# currentBaseBoard_v7.net
KiCad netlist of a schematic drawn in EAGLE
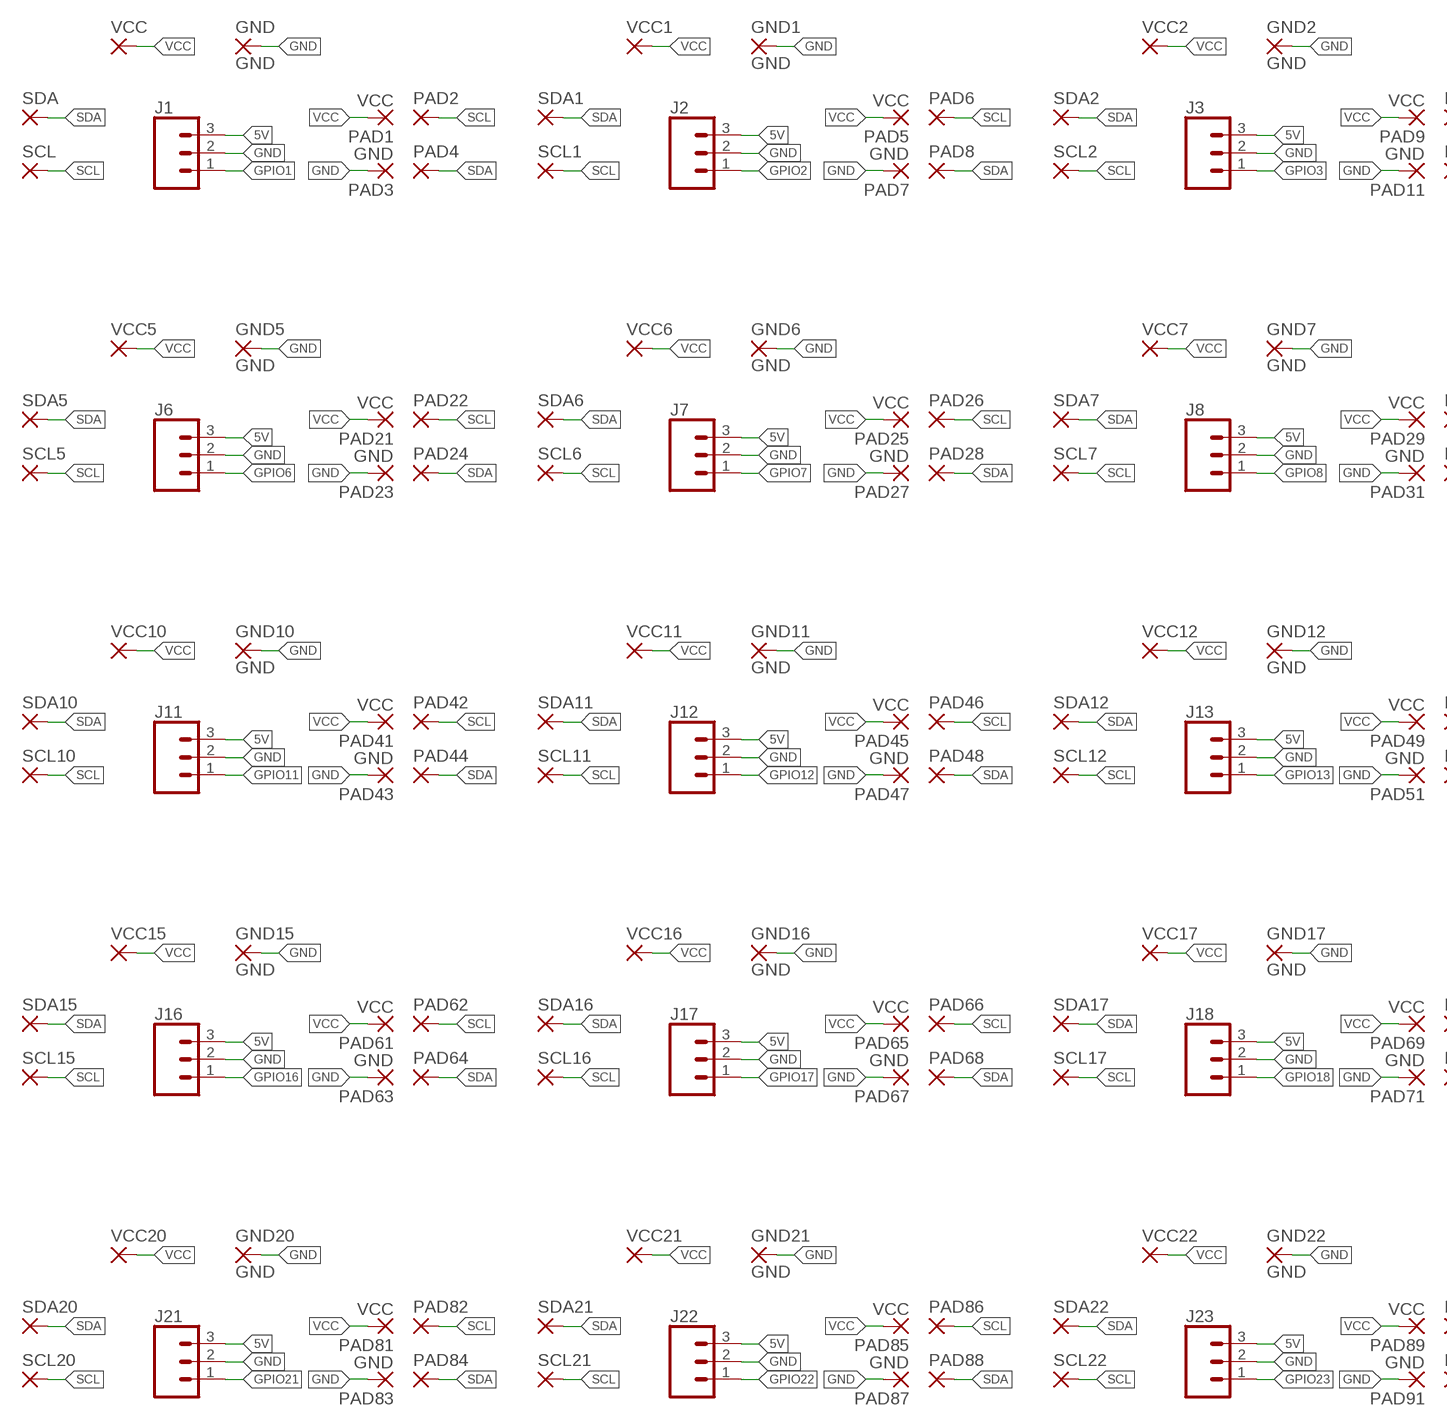
[diagram p0: schematic, sheet 1, part 1 of 2]
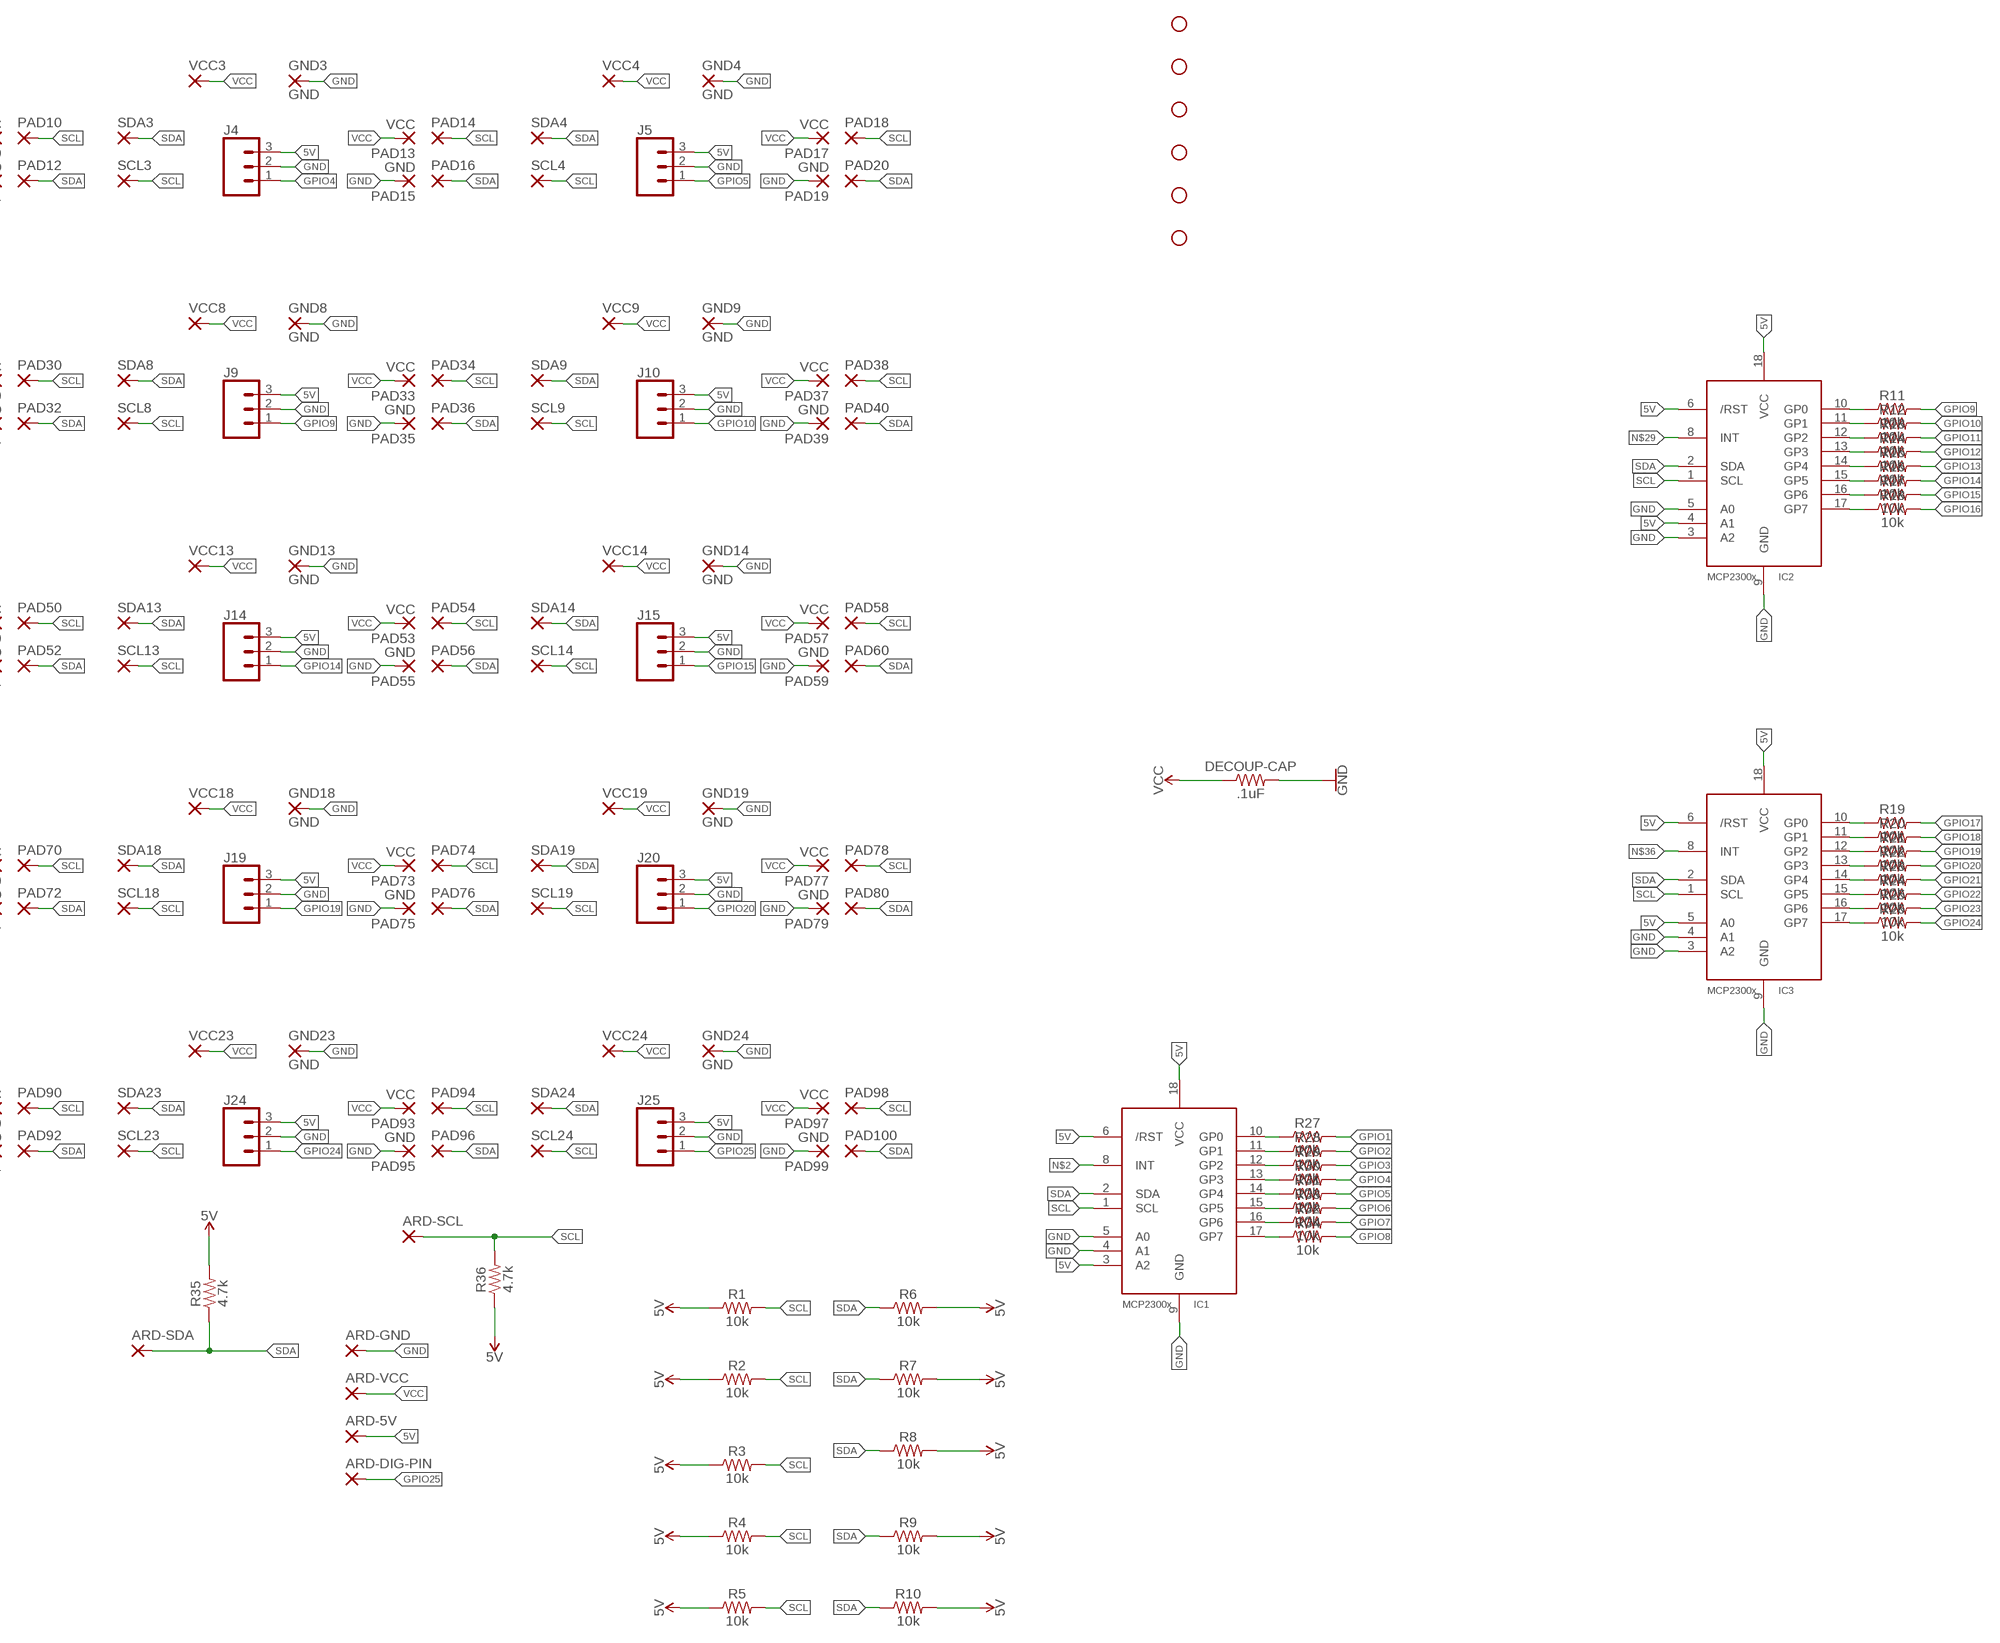
[diagram p1: schematic, sheet 1, part 2 of 2]

(export (version "E")
  (design (tool "Eeschema 10.0.6"))
  (components
    (comp (ref "ARD-5V")
      (value "2,15/1,0")
      (footprint "eagle-import:2,15_1,0")
      (libsource (lib "eagle-import") (part "2,15/1,0"))
    )
    (comp (ref "ARD-DIG-PIN")
      (value "2,15/1,0")
      (footprint "eagle-import:2,15_1,0")
      (libsource (lib "eagle-import") (part "2,15/1,0"))
    )
    (comp (ref "ARD-GND")
      (value "2,15/1,0")
      (footprint "eagle-import:2,15_1,0")
      (libsource (lib "eagle-import") (part "2,15/1,0"))
    )
    (comp (ref "ARD-SCL")
      (value "2,15/1,0")
      (footprint "eagle-import:2,15_1,0")
      (libsource (lib "eagle-import") (part "2,15/1,0"))
    )
    (comp (ref "ARD-SDA")
      (value "2,15/1,0")
      (footprint "eagle-import:2,15_1,0")
      (libsource (lib "eagle-import") (part "2,15/1,0"))
    )
    (comp (ref "ARD-VCC")
      (value "2,15/1,0")
      (footprint "eagle-import:2,15_1,0")
      (libsource (lib "eagle-import") (part "2,15/1,0"))
    )
    (comp (ref "DECOUP-CAP")
      (value ".1uF")
      (footprint "eagle-import:AXIAL-0.3")
      (libsource (lib "eagle-import") (part "10KOHM-HORIZ-1/6W-5%"))
    )
    (comp (ref "GND")
      (value "GND")
      (footprint "eagle-import:2,15_1,0")
      (libsource (lib "eagle-import") (part "2,15/1,0"))
    )
    (comp (ref "GND1")
      (value "GND")
      (footprint "eagle-import:2,15_1,0")
      (libsource (lib "eagle-import") (part "2,15/1,0"))
    )
    (comp (ref "GND2")
      (value "GND")
      (footprint "eagle-import:2,15_1,0")
      (libsource (lib "eagle-import") (part "2,15/1,0"))
    )
    (comp (ref "GND3")
      (value "GND")
      (footprint "eagle-import:2,15_1,0")
      (libsource (lib "eagle-import") (part "2,15/1,0"))
    )
    (comp (ref "GND4")
      (value "GND")
      (footprint "eagle-import:2,15_1,0")
      (libsource (lib "eagle-import") (part "2,15/1,0"))
    )
    (comp (ref "GND5")
      (value "GND")
      (footprint "eagle-import:2,15_1,0")
      (libsource (lib "eagle-import") (part "2,15/1,0"))
    )
    (comp (ref "GND6")
      (value "GND")
      (footprint "eagle-import:2,15_1,0")
      (libsource (lib "eagle-import") (part "2,15/1,0"))
    )
    (comp (ref "GND7")
      (value "GND")
      (footprint "eagle-import:2,15_1,0")
      (libsource (lib "eagle-import") (part "2,15/1,0"))
    )
    (comp (ref "GND8")
      (value "GND")
      (footprint "eagle-import:2,15_1,0")
      (libsource (lib "eagle-import") (part "2,15/1,0"))
    )
    (comp (ref "GND9")
      (value "GND")
      (footprint "eagle-import:2,15_1,0")
      (libsource (lib "eagle-import") (part "2,15/1,0"))
    )
    (comp (ref "GND10")
      (value "GND")
      (footprint "eagle-import:2,15_1,0")
      (libsource (lib "eagle-import") (part "2,15/1,0"))
    )
    (comp (ref "GND11")
      (value "GND")
      (footprint "eagle-import:2,15_1,0")
      (libsource (lib "eagle-import") (part "2,15/1,0"))
    )
    (comp (ref "GND12")
      (value "GND")
      (footprint "eagle-import:2,15_1,0")
      (libsource (lib "eagle-import") (part "2,15/1,0"))
    )
    (comp (ref "GND13")
      (value "GND")
      (footprint "eagle-import:2,15_1,0")
      (libsource (lib "eagle-import") (part "2,15/1,0"))
    )
    (comp (ref "GND14")
      (value "GND")
      (footprint "eagle-import:2,15_1,0")
      (libsource (lib "eagle-import") (part "2,15/1,0"))
    )
    (comp (ref "GND15")
      (value "GND")
      (footprint "eagle-import:2,15_1,0")
      (libsource (lib "eagle-import") (part "2,15/1,0"))
    )
    (comp (ref "GND16")
      (value "GND")
      (footprint "eagle-import:2,15_1,0")
      (libsource (lib "eagle-import") (part "2,15/1,0"))
    )
    (comp (ref "GND17")
      (value "GND")
      (footprint "eagle-import:2,15_1,0")
      (libsource (lib "eagle-import") (part "2,15/1,0"))
    )
    (comp (ref "GND18")
      (value "GND")
      (footprint "eagle-import:2,15_1,0")
      (libsource (lib "eagle-import") (part "2,15/1,0"))
    )
    (comp (ref "GND19")
      (value "GND")
      (footprint "eagle-import:2,15_1,0")
      (libsource (lib "eagle-import") (part "2,15/1,0"))
    )
    (comp (ref "GND20")
      (value "GND")
      (footprint "eagle-import:2,15_1,0")
      (libsource (lib "eagle-import") (part "2,15/1,0"))
    )
    (comp (ref "GND21")
      (value "GND")
      (footprint "eagle-import:2,15_1,0")
      (libsource (lib "eagle-import") (part "2,15/1,0"))
    )
    (comp (ref "GND22")
      (value "GND")
      (footprint "eagle-import:2,15_1,0")
      (libsource (lib "eagle-import") (part "2,15/1,0"))
    )
    (comp (ref "GND23")
      (value "GND")
      (footprint "eagle-import:2,15_1,0")
      (libsource (lib "eagle-import") (part "2,15/1,0"))
    )
    (comp (ref "GND24")
      (value "GND")
      (footprint "eagle-import:2,15_1,0")
      (libsource (lib "eagle-import") (part "2,15/1,0"))
    )
    (comp (ref "H1")
      (value "STAND-OFF")
      (footprint "eagle-import:STAND-OFF")
      (libsource (lib "eagle-import") (part "STAND-OFF"))
    )
    (comp (ref "H2")
      (value "STAND-OFF")
      (footprint "eagle-import:STAND-OFF")
      (libsource (lib "eagle-import") (part "STAND-OFF"))
    )
    (comp (ref "H3")
      (value "STAND-OFF")
      (footprint "eagle-import:STAND-OFF")
      (libsource (lib "eagle-import") (part "STAND-OFF"))
    )
    (comp (ref "H4")
      (value "STAND-OFF")
      (footprint "eagle-import:STAND-OFF")
      (libsource (lib "eagle-import") (part "STAND-OFF"))
    )
    (comp (ref "H5")
      (value "STAND-OFF")
      (footprint "eagle-import:STAND-OFF")
      (libsource (lib "eagle-import") (part "STAND-OFF"))
    )
    (comp (ref "H6")
      (value "STAND-OFF")
      (footprint "eagle-import:STAND-OFF")
      (libsource (lib "eagle-import") (part "STAND-OFF"))
    )
    (comp (ref "IC1")
      (value "MCP23008/P")
      (footprint "eagle-import:DIL18")
      (libsource (lib "eagle-import") (part "MCP23008/P"))
    )
    (comp (ref "IC2")
      (value "MCP23008/P")
      (footprint "eagle-import:DIL18")
      (libsource (lib "eagle-import") (part "MCP23008/P"))
    )
    (comp (ref "IC3")
      (value "MCP23008/P")
      (footprint "eagle-import:DIL18")
      (libsource (lib "eagle-import") (part "MCP23008/P"))
    )
    (comp (ref "J1")
      (value "CONN_03")
      (footprint "eagle-import:1X03")
      (libsource (lib "eagle-import") (part "CONN_03"))
    )
    (comp (ref "J2")
      (value "CONN_03")
      (footprint "eagle-import:1X03")
      (libsource (lib "eagle-import") (part "CONN_03"))
    )
    (comp (ref "J3")
      (value "CONN_03")
      (footprint "eagle-import:1X03")
      (libsource (lib "eagle-import") (part "CONN_03"))
    )
    (comp (ref "J4")
      (value "CONN_03")
      (footprint "eagle-import:1X03")
      (libsource (lib "eagle-import") (part "CONN_03"))
    )
    (comp (ref "J5")
      (value "CONN_03")
      (footprint "eagle-import:1X03")
      (libsource (lib "eagle-import") (part "CONN_03"))
    )
    (comp (ref "J6")
      (value "CONN_03")
      (footprint "eagle-import:1X03")
      (libsource (lib "eagle-import") (part "CONN_03"))
    )
    (comp (ref "J7")
      (value "CONN_03")
      (footprint "eagle-import:1X03")
      (libsource (lib "eagle-import") (part "CONN_03"))
    )
    (comp (ref "J8")
      (value "CONN_03")
      (footprint "eagle-import:1X03")
      (libsource (lib "eagle-import") (part "CONN_03"))
    )
    (comp (ref "J9")
      (value "CONN_03")
      (footprint "eagle-import:1X03")
      (libsource (lib "eagle-import") (part "CONN_03"))
    )
    (comp (ref "J10")
      (value "CONN_03")
      (footprint "eagle-import:1X03")
      (libsource (lib "eagle-import") (part "CONN_03"))
    )
    (comp (ref "J11")
      (value "CONN_03")
      (footprint "eagle-import:1X03")
      (libsource (lib "eagle-import") (part "CONN_03"))
    )
    (comp (ref "J12")
      (value "CONN_03")
      (footprint "eagle-import:1X03")
      (libsource (lib "eagle-import") (part "CONN_03"))
    )
    (comp (ref "J13")
      (value "CONN_03")
      (footprint "eagle-import:1X03")
      (libsource (lib "eagle-import") (part "CONN_03"))
    )
    (comp (ref "J14")
      (value "CONN_03")
      (footprint "eagle-import:1X03")
      (libsource (lib "eagle-import") (part "CONN_03"))
    )
    (comp (ref "J15")
      (value "CONN_03")
      (footprint "eagle-import:1X03")
      (libsource (lib "eagle-import") (part "CONN_03"))
    )
    (comp (ref "J16")
      (value "CONN_03")
      (footprint "eagle-import:1X03")
      (libsource (lib "eagle-import") (part "CONN_03"))
    )
    (comp (ref "J17")
      (value "CONN_03")
      (footprint "eagle-import:1X03")
      (libsource (lib "eagle-import") (part "CONN_03"))
    )
    (comp (ref "J18")
      (value "CONN_03")
      (footprint "eagle-import:1X03")
      (libsource (lib "eagle-import") (part "CONN_03"))
    )
    (comp (ref "J19")
      (value "CONN_03")
      (footprint "eagle-import:1X03")
      (libsource (lib "eagle-import") (part "CONN_03"))
    )
    (comp (ref "J20")
      (value "CONN_03")
      (footprint "eagle-import:1X03")
      (libsource (lib "eagle-import") (part "CONN_03"))
    )
    (comp (ref "J21")
      (value "CONN_03")
      (footprint "eagle-import:1X03")
      (libsource (lib "eagle-import") (part "CONN_03"))
    )
    (comp (ref "J22")
      (value "CONN_03")
      (footprint "eagle-import:1X03")
      (libsource (lib "eagle-import") (part "CONN_03"))
    )
    (comp (ref "J23")
      (value "CONN_03")
      (footprint "eagle-import:1X03")
      (libsource (lib "eagle-import") (part "CONN_03"))
    )
    (comp (ref "J24")
      (value "CONN_03")
      (footprint "eagle-import:1X03")
      (libsource (lib "eagle-import") (part "CONN_03"))
    )
    (comp (ref "J25")
      (value "CONN_03")
      (footprint "eagle-import:1X03")
      (libsource (lib "eagle-import") (part "CONN_03"))
    )
    (comp (ref "PAD1")
      (value "VCC")
      (footprint "eagle-import:2,15_1,0")
      (libsource (lib "eagle-import") (part "2,15/1,0"))
    )
    (comp (ref "PAD2")
      (value "2,15/1,0")
      (footprint "eagle-import:2,15_1,0")
      (libsource (lib "eagle-import") (part "2,15/1,0"))
    )
    (comp (ref "PAD3")
      (value "GND")
      (footprint "eagle-import:2,15_1,0")
      (libsource (lib "eagle-import") (part "2,15/1,0"))
    )
    (comp (ref "PAD4")
      (value "2,15/1,0")
      (footprint "eagle-import:2,15_1,0")
      (libsource (lib "eagle-import") (part "2,15/1,0"))
    )
    (comp (ref "PAD5")
      (value "VCC")
      (footprint "eagle-import:2,15_1,0")
      (libsource (lib "eagle-import") (part "2,15/1,0"))
    )
    (comp (ref "PAD6")
      (value "2,15/1,0")
      (footprint "eagle-import:2,15_1,0")
      (libsource (lib "eagle-import") (part "2,15/1,0"))
    )
    (comp (ref "PAD7")
      (value "GND")
      (footprint "eagle-import:2,15_1,0")
      (libsource (lib "eagle-import") (part "2,15/1,0"))
    )
    (comp (ref "PAD8")
      (value "2,15/1,0")
      (footprint "eagle-import:2,15_1,0")
      (libsource (lib "eagle-import") (part "2,15/1,0"))
    )
    (comp (ref "PAD9")
      (value "VCC")
      (footprint "eagle-import:2,15_1,0")
      (libsource (lib "eagle-import") (part "2,15/1,0"))
    )
    (comp (ref "PAD10")
      (value "2,15/1,0")
      (footprint "eagle-import:2,15_1,0")
      (libsource (lib "eagle-import") (part "2,15/1,0"))
    )
    (comp (ref "PAD11")
      (value "GND")
      (footprint "eagle-import:2,15_1,0")
      (libsource (lib "eagle-import") (part "2,15/1,0"))
    )
    (comp (ref "PAD12")
      (value "2,15/1,0")
      (footprint "eagle-import:2,15_1,0")
      (libsource (lib "eagle-import") (part "2,15/1,0"))
    )
    (comp (ref "PAD13")
      (value "VCC")
      (footprint "eagle-import:2,15_1,0")
      (libsource (lib "eagle-import") (part "2,15/1,0"))
    )
    (comp (ref "PAD14")
      (value "2,15/1,0")
      (footprint "eagle-import:2,15_1,0")
      (libsource (lib "eagle-import") (part "2,15/1,0"))
    )
    (comp (ref "PAD15")
      (value "GND")
      (footprint "eagle-import:2,15_1,0")
      (libsource (lib "eagle-import") (part "2,15/1,0"))
    )
    (comp (ref "PAD16")
      (value "2,15/1,0")
      (footprint "eagle-import:2,15_1,0")
      (libsource (lib "eagle-import") (part "2,15/1,0"))
    )
    (comp (ref "PAD17")
      (value "VCC")
      (footprint "eagle-import:2,15_1,0")
      (libsource (lib "eagle-import") (part "2,15/1,0"))
    )
    (comp (ref "PAD18")
      (value "2,15/1,0")
      (footprint "eagle-import:2,15_1,0")
      (libsource (lib "eagle-import") (part "2,15/1,0"))
    )
    (comp (ref "PAD19")
      (value "GND")
      (footprint "eagle-import:2,15_1,0")
      (libsource (lib "eagle-import") (part "2,15/1,0"))
    )
    (comp (ref "PAD20")
      (value "2,15/1,0")
      (footprint "eagle-import:2,15_1,0")
      (libsource (lib "eagle-import") (part "2,15/1,0"))
    )
    (comp (ref "PAD21")
      (value "VCC")
      (footprint "eagle-import:2,15_1,0")
      (libsource (lib "eagle-import") (part "2,15/1,0"))
    )
    (comp (ref "PAD22")
      (value "2,15/1,0")
      (footprint "eagle-import:2,15_1,0")
      (libsource (lib "eagle-import") (part "2,15/1,0"))
    )
    (comp (ref "PAD23")
      (value "GND")
      (footprint "eagle-import:2,15_1,0")
      (libsource (lib "eagle-import") (part "2,15/1,0"))
    )
    (comp (ref "PAD24")
      (value "2,15/1,0")
      (footprint "eagle-import:2,15_1,0")
      (libsource (lib "eagle-import") (part "2,15/1,0"))
    )
    (comp (ref "PAD25")
      (value "VCC")
      (footprint "eagle-import:2,15_1,0")
      (libsource (lib "eagle-import") (part "2,15/1,0"))
    )
    (comp (ref "PAD26")
      (value "2,15/1,0")
      (footprint "eagle-import:2,15_1,0")
      (libsource (lib "eagle-import") (part "2,15/1,0"))
    )
    (comp (ref "PAD27")
      (value "GND")
      (footprint "eagle-import:2,15_1,0")
      (libsource (lib "eagle-import") (part "2,15/1,0"))
    )
    (comp (ref "PAD28")
      (value "2,15/1,0")
      (footprint "eagle-import:2,15_1,0")
      (libsource (lib "eagle-import") (part "2,15/1,0"))
    )
    (comp (ref "PAD29")
      (value "VCC")
      (footprint "eagle-import:2,15_1,0")
      (libsource (lib "eagle-import") (part "2,15/1,0"))
    )
    (comp (ref "PAD30")
      (value "2,15/1,0")
      (footprint "eagle-import:2,15_1,0")
      (libsource (lib "eagle-import") (part "2,15/1,0"))
    )
    (comp (ref "PAD31")
      (value "GND")
      (footprint "eagle-import:2,15_1,0")
      (libsource (lib "eagle-import") (part "2,15/1,0"))
    )
    (comp (ref "PAD32")
      (value "2,15/1,0")
      (footprint "eagle-import:2,15_1,0")
      (libsource (lib "eagle-import") (part "2,15/1,0"))
    )
    (comp (ref "PAD33")
      (value "VCC")
      (footprint "eagle-import:2,15_1,0")
      (libsource (lib "eagle-import") (part "2,15/1,0"))
    )
    (comp (ref "PAD34")
      (value "2,15/1,0")
      (footprint "eagle-import:2,15_1,0")
      (libsource (lib "eagle-import") (part "2,15/1,0"))
    )
    (comp (ref "PAD35")
      (value "GND")
      (footprint "eagle-import:2,15_1,0")
      (libsource (lib "eagle-import") (part "2,15/1,0"))
    )
    (comp (ref "PAD36")
      (value "2,15/1,0")
      (footprint "eagle-import:2,15_1,0")
      (libsource (lib "eagle-import") (part "2,15/1,0"))
    )
    (comp (ref "PAD37")
      (value "VCC")
      (footprint "eagle-import:2,15_1,0")
      (libsource (lib "eagle-import") (part "2,15/1,0"))
    )
    (comp (ref "PAD38")
      (value "2,15/1,0")
      (footprint "eagle-import:2,15_1,0")
      (libsource (lib "eagle-import") (part "2,15/1,0"))
    )
    (comp (ref "PAD39")
      (value "GND")
      (footprint "eagle-import:2,15_1,0")
      (libsource (lib "eagle-import") (part "2,15/1,0"))
    )
    (comp (ref "PAD40")
      (value "2,15/1,0")
      (footprint "eagle-import:2,15_1,0")
      (libsource (lib "eagle-import") (part "2,15/1,0"))
    )
    (comp (ref "PAD41")
      (value "VCC")
      (footprint "eagle-import:2,15_1,0")
      (libsource (lib "eagle-import") (part "2,15/1,0"))
    )
    (comp (ref "PAD42")
      (value "2,15/1,0")
      (footprint "eagle-import:2,15_1,0")
      (libsource (lib "eagle-import") (part "2,15/1,0"))
    )
    (comp (ref "PAD43")
      (value "GND")
      (footprint "eagle-import:2,15_1,0")
      (libsource (lib "eagle-import") (part "2,15/1,0"))
    )
    (comp (ref "PAD44")
      (value "2,15/1,0")
      (footprint "eagle-import:2,15_1,0")
      (libsource (lib "eagle-import") (part "2,15/1,0"))
    )
    (comp (ref "PAD45")
      (value "VCC")
      (footprint "eagle-import:2,15_1,0")
      (libsource (lib "eagle-import") (part "2,15/1,0"))
    )
    (comp (ref "PAD46")
      (value "2,15/1,0")
      (footprint "eagle-import:2,15_1,0")
      (libsource (lib "eagle-import") (part "2,15/1,0"))
    )
    (comp (ref "PAD47")
      (value "GND")
      (footprint "eagle-import:2,15_1,0")
      (libsource (lib "eagle-import") (part "2,15/1,0"))
    )
    (comp (ref "PAD48")
      (value "2,15/1,0")
      (footprint "eagle-import:2,15_1,0")
      (libsource (lib "eagle-import") (part "2,15/1,0"))
    )
    (comp (ref "PAD49")
      (value "VCC")
      (footprint "eagle-import:2,15_1,0")
      (libsource (lib "eagle-import") (part "2,15/1,0"))
    )
    (comp (ref "PAD50")
      (value "2,15/1,0")
      (footprint "eagle-import:2,15_1,0")
      (libsource (lib "eagle-import") (part "2,15/1,0"))
    )
    (comp (ref "PAD51")
      (value "GND")
      (footprint "eagle-import:2,15_1,0")
      (libsource (lib "eagle-import") (part "2,15/1,0"))
    )
    (comp (ref "PAD52")
      (value "2,15/1,0")
      (footprint "eagle-import:2,15_1,0")
      (libsource (lib "eagle-import") (part "2,15/1,0"))
    )
    (comp (ref "PAD53")
      (value "VCC")
      (footprint "eagle-import:2,15_1,0")
      (libsource (lib "eagle-import") (part "2,15/1,0"))
    )
    (comp (ref "PAD54")
      (value "2,15/1,0")
      (footprint "eagle-import:2,15_1,0")
      (libsource (lib "eagle-import") (part "2,15/1,0"))
    )
    (comp (ref "PAD55")
      (value "GND")
      (footprint "eagle-import:2,15_1,0")
      (libsource (lib "eagle-import") (part "2,15/1,0"))
    )
    (comp (ref "PAD56")
      (value "2,15/1,0")
      (footprint "eagle-import:2,15_1,0")
      (libsource (lib "eagle-import") (part "2,15/1,0"))
    )
    (comp (ref "PAD57")
      (value "VCC")
      (footprint "eagle-import:2,15_1,0")
      (libsource (lib "eagle-import") (part "2,15/1,0"))
    )
    (comp (ref "PAD58")
      (value "2,15/1,0")
      (footprint "eagle-import:2,15_1,0")
      (libsource (lib "eagle-import") (part "2,15/1,0"))
    )
    (comp (ref "PAD59")
      (value "GND")
      (footprint "eagle-import:2,15_1,0")
      (libsource (lib "eagle-import") (part "2,15/1,0"))
    )
    (comp (ref "PAD60")
      (value "2,15/1,0")
      (footprint "eagle-import:2,15_1,0")
      (libsource (lib "eagle-import") (part "2,15/1,0"))
    )
    (comp (ref "PAD61")
      (value "VCC")
      (footprint "eagle-import:2,15_1,0")
      (libsource (lib "eagle-import") (part "2,15/1,0"))
    )
    (comp (ref "PAD62")
      (value "2,15/1,0")
      (footprint "eagle-import:2,15_1,0")
      (libsource (lib "eagle-import") (part "2,15/1,0"))
    )
    (comp (ref "PAD63")
      (value "GND")
      (footprint "eagle-import:2,15_1,0")
      (libsource (lib "eagle-import") (part "2,15/1,0"))
    )
    (comp (ref "PAD64")
      (value "2,15/1,0")
      (footprint "eagle-import:2,15_1,0")
      (libsource (lib "eagle-import") (part "2,15/1,0"))
    )
    (comp (ref "PAD65")
      (value "VCC")
      (footprint "eagle-import:2,15_1,0")
      (libsource (lib "eagle-import") (part "2,15/1,0"))
    )
    (comp (ref "PAD66")
      (value "2,15/1,0")
      (footprint "eagle-import:2,15_1,0")
      (libsource (lib "eagle-import") (part "2,15/1,0"))
    )
    (comp (ref "PAD67")
      (value "GND")
      (footprint "eagle-import:2,15_1,0")
      (libsource (lib "eagle-import") (part "2,15/1,0"))
    )
    (comp (ref "PAD68")
      (value "2,15/1,0")
      (footprint "eagle-import:2,15_1,0")
      (libsource (lib "eagle-import") (part "2,15/1,0"))
    )
    (comp (ref "PAD69")
      (value "VCC")
      (footprint "eagle-import:2,15_1,0")
      (libsource (lib "eagle-import") (part "2,15/1,0"))
    )
    (comp (ref "PAD70")
      (value "2,15/1,0")
      (footprint "eagle-import:2,15_1,0")
      (libsource (lib "eagle-import") (part "2,15/1,0"))
    )
    (comp (ref "PAD71")
      (value "GND")
      (footprint "eagle-import:2,15_1,0")
      (libsource (lib "eagle-import") (part "2,15/1,0"))
    )
    (comp (ref "PAD72")
      (value "2,15/1,0")
      (footprint "eagle-import:2,15_1,0")
      (libsource (lib "eagle-import") (part "2,15/1,0"))
    )
    (comp (ref "PAD73")
      (value "VCC")
      (footprint "eagle-import:2,15_1,0")
      (libsource (lib "eagle-import") (part "2,15/1,0"))
    )
    (comp (ref "PAD74")
      (value "2,15/1,0")
      (footprint "eagle-import:2,15_1,0")
      (libsource (lib "eagle-import") (part "2,15/1,0"))
    )
    (comp (ref "PAD75")
      (value "GND")
      (footprint "eagle-import:2,15_1,0")
      (libsource (lib "eagle-import") (part "2,15/1,0"))
    )
    (comp (ref "PAD76")
      (value "2,15/1,0")
      (footprint "eagle-import:2,15_1,0")
      (libsource (lib "eagle-import") (part "2,15/1,0"))
    )
    (comp (ref "PAD77")
      (value "VCC")
      (footprint "eagle-import:2,15_1,0")
      (libsource (lib "eagle-import") (part "2,15/1,0"))
    )
    (comp (ref "PAD78")
      (value "2,15/1,0")
      (footprint "eagle-import:2,15_1,0")
      (libsource (lib "eagle-import") (part "2,15/1,0"))
    )
    (comp (ref "PAD79")
      (value "GND")
      (footprint "eagle-import:2,15_1,0")
      (libsource (lib "eagle-import") (part "2,15/1,0"))
    )
    (comp (ref "PAD80")
      (value "2,15/1,0")
      (footprint "eagle-import:2,15_1,0")
      (libsource (lib "eagle-import") (part "2,15/1,0"))
    )
    (comp (ref "PAD81")
      (value "VCC")
      (footprint "eagle-import:2,15_1,0")
      (libsource (lib "eagle-import") (part "2,15/1,0"))
    )
    (comp (ref "PAD82")
      (value "2,15/1,0")
      (footprint "eagle-import:2,15_1,0")
      (libsource (lib "eagle-import") (part "2,15/1,0"))
    )
    (comp (ref "PAD83")
      (value "GND")
      (footprint "eagle-import:2,15_1,0")
      (libsource (lib "eagle-import") (part "2,15/1,0"))
    )
    (comp (ref "PAD84")
      (value "2,15/1,0")
      (footprint "eagle-import:2,15_1,0")
      (libsource (lib "eagle-import") (part "2,15/1,0"))
    )
    (comp (ref "PAD85")
      (value "VCC")
      (footprint "eagle-import:2,15_1,0")
      (libsource (lib "eagle-import") (part "2,15/1,0"))
    )
    (comp (ref "PAD86")
      (value "2,15/1,0")
      (footprint "eagle-import:2,15_1,0")
      (libsource (lib "eagle-import") (part "2,15/1,0"))
    )
    (comp (ref "PAD87")
      (value "GND")
      (footprint "eagle-import:2,15_1,0")
      (libsource (lib "eagle-import") (part "2,15/1,0"))
    )
    (comp (ref "PAD88")
      (value "2,15/1,0")
      (footprint "eagle-import:2,15_1,0")
      (libsource (lib "eagle-import") (part "2,15/1,0"))
    )
    (comp (ref "PAD89")
      (value "VCC")
      (footprint "eagle-import:2,15_1,0")
      (libsource (lib "eagle-import") (part "2,15/1,0"))
    )
    (comp (ref "PAD90")
      (value "2,15/1,0")
      (footprint "eagle-import:2,15_1,0")
      (libsource (lib "eagle-import") (part "2,15/1,0"))
    )
    (comp (ref "PAD91")
      (value "GND")
      (footprint "eagle-import:2,15_1,0")
      (libsource (lib "eagle-import") (part "2,15/1,0"))
    )
    (comp (ref "PAD92")
      (value "2,15/1,0")
      (footprint "eagle-import:2,15_1,0")
      (libsource (lib "eagle-import") (part "2,15/1,0"))
    )
    (comp (ref "PAD93")
      (value "VCC")
      (footprint "eagle-import:2,15_1,0")
      (libsource (lib "eagle-import") (part "2,15/1,0"))
    )
    (comp (ref "PAD94")
      (value "2,15/1,0")
      (footprint "eagle-import:2,15_1,0")
      (libsource (lib "eagle-import") (part "2,15/1,0"))
    )
    (comp (ref "PAD95")
      (value "GND")
      (footprint "eagle-import:2,15_1,0")
      (libsource (lib "eagle-import") (part "2,15/1,0"))
    )
    (comp (ref "PAD96")
      (value "2,15/1,0")
      (footprint "eagle-import:2,15_1,0")
      (libsource (lib "eagle-import") (part "2,15/1,0"))
    )
    (comp (ref "PAD97")
      (value "VCC")
      (footprint "eagle-import:2,15_1,0")
      (libsource (lib "eagle-import") (part "2,15/1,0"))
    )
    (comp (ref "PAD98")
      (value "2,15/1,0")
      (footprint "eagle-import:2,15_1,0")
      (libsource (lib "eagle-import") (part "2,15/1,0"))
    )
    (comp (ref "PAD99")
      (value "GND")
      (footprint "eagle-import:2,15_1,0")
      (libsource (lib "eagle-import") (part "2,15/1,0"))
    )
    (comp (ref "PAD100")
      (value "2,15/1,0")
      (footprint "eagle-import:2,15_1,0")
      (libsource (lib "eagle-import") (part "2,15/1,0"))
    )
    (comp (ref "R1")
      (value "10k")
      (footprint "eagle-import:AXIAL-0.3")
      (libsource (lib "eagle-import") (part "10KOHM-HORIZ-1/4W-1%"))
    )
    (comp (ref "R2")
      (value "10k")
      (footprint "eagle-import:AXIAL-0.3")
      (libsource (lib "eagle-import") (part "10KOHM-HORIZ-1/4W-1%"))
    )
    (comp (ref "R3")
      (value "10k")
      (footprint "eagle-import:AXIAL-0.3")
      (libsource (lib "eagle-import") (part "10KOHM-HORIZ-1/4W-1%"))
    )
    (comp (ref "R4")
      (value "10k")
      (footprint "eagle-import:AXIAL-0.3")
      (libsource (lib "eagle-import") (part "10KOHM-HORIZ-1/4W-1%"))
    )
    (comp (ref "R5")
      (value "10k")
      (footprint "eagle-import:AXIAL-0.3")
      (libsource (lib "eagle-import") (part "10KOHM-HORIZ-1/4W-1%"))
    )
    (comp (ref "R6")
      (value "10k")
      (footprint "eagle-import:AXIAL-0.3")
      (libsource (lib "eagle-import") (part "10KOHM-HORIZ-1/4W-1%"))
    )
    (comp (ref "R7")
      (value "10k")
      (footprint "eagle-import:AXIAL-0.3")
      (libsource (lib "eagle-import") (part "10KOHM-HORIZ-1/4W-1%"))
    )
    (comp (ref "R8")
      (value "10k")
      (footprint "eagle-import:AXIAL-0.3")
      (libsource (lib "eagle-import") (part "10KOHM-HORIZ-1/4W-1%"))
    )
    (comp (ref "R9")
      (value "10k")
      (footprint "eagle-import:AXIAL-0.3")
      (libsource (lib "eagle-import") (part "10KOHM-HORIZ-1/4W-1%"))
    )
    (comp (ref "R10")
      (value "10k")
      (footprint "eagle-import:AXIAL-0.3")
      (libsource (lib "eagle-import") (part "10KOHM-HORIZ-1/4W-1%"))
    )
    (comp (ref "R11")
      (value "10k")
      (footprint "eagle-import:AXIAL-0.3")
      (libsource (lib "eagle-import") (part "10KOHM-HORIZ-1/6W-5%"))
    )
    (comp (ref "R12")
      (value "10k")
      (footprint "eagle-import:AXIAL-0.3")
      (libsource (lib "eagle-import") (part "10KOHM-HORIZ-1/6W-5%"))
    )
    (comp (ref "R13")
      (value "10k")
      (footprint "eagle-import:AXIAL-0.3")
      (libsource (lib "eagle-import") (part "10KOHM-HORIZ-1/6W-5%"))
    )
    (comp (ref "R14")
      (value "10k")
      (footprint "eagle-import:AXIAL-0.3")
      (libsource (lib "eagle-import") (part "10KOHM-HORIZ-1/6W-5%"))
    )
    (comp (ref "R15")
      (value "10k")
      (footprint "eagle-import:AXIAL-0.3")
      (libsource (lib "eagle-import") (part "10KOHM-HORIZ-1/6W-5%"))
    )
    (comp (ref "R16")
      (value "10k")
      (footprint "eagle-import:AXIAL-0.3")
      (libsource (lib "eagle-import") (part "10KOHM-HORIZ-1/6W-5%"))
    )
    (comp (ref "R17")
      (value "10k")
      (footprint "eagle-import:AXIAL-0.3")
      (libsource (lib "eagle-import") (part "10KOHM-HORIZ-1/6W-5%"))
    )
    (comp (ref "R18")
      (value "10k")
      (footprint "eagle-import:AXIAL-0.3")
      (libsource (lib "eagle-import") (part "10KOHM-HORIZ-1/6W-5%"))
    )
    (comp (ref "R19")
      (value "10k")
      (footprint "eagle-import:AXIAL-0.3")
      (libsource (lib "eagle-import") (part "10KOHM-HORIZ-1/6W-5%"))
    )
    (comp (ref "R20")
      (value "10k")
      (footprint "eagle-import:AXIAL-0.3")
      (libsource (lib "eagle-import") (part "10KOHM-HORIZ-1/6W-5%"))
    )
    (comp (ref "R21")
      (value "10k")
      (footprint "eagle-import:AXIAL-0.3")
      (libsource (lib "eagle-import") (part "10KOHM-HORIZ-1/6W-5%"))
    )
    (comp (ref "R22")
      (value "10k")
      (footprint "eagle-import:AXIAL-0.3")
      (libsource (lib "eagle-import") (part "10KOHM-HORIZ-1/6W-5%"))
    )
    (comp (ref "R23")
      (value "10k")
      (footprint "eagle-import:AXIAL-0.3")
      (libsource (lib "eagle-import") (part "10KOHM-HORIZ-1/6W-5%"))
    )
    (comp (ref "R24")
      (value "10k")
      (footprint "eagle-import:AXIAL-0.3")
      (libsource (lib "eagle-import") (part "10KOHM-HORIZ-1/6W-5%"))
    )
    (comp (ref "R25")
      (value "10k")
      (footprint "eagle-import:AXIAL-0.3")
      (libsource (lib "eagle-import") (part "10KOHM-HORIZ-1/6W-5%"))
    )
    (comp (ref "R26")
      (value "10k")
      (footprint "eagle-import:AXIAL-0.3")
      (libsource (lib "eagle-import") (part "10KOHM-HORIZ-1/6W-5%"))
    )
    (comp (ref "R27")
      (value "10k")
      (footprint "eagle-import:AXIAL-0.3")
      (libsource (lib "eagle-import") (part "10KOHM-HORIZ-1/6W-5%"))
    )
    (comp (ref "R28")
      (value "10k")
      (footprint "eagle-import:AXIAL-0.3")
      (libsource (lib "eagle-import") (part "10KOHM-HORIZ-1/6W-5%"))
    )
    (comp (ref "R29")
      (value "10k")
      (footprint "eagle-import:AXIAL-0.3")
      (libsource (lib "eagle-import") (part "10KOHM-HORIZ-1/6W-5%"))
    )
    (comp (ref "R30")
      (value "10k")
      (footprint "eagle-import:AXIAL-0.3")
      (libsource (lib "eagle-import") (part "10KOHM-HORIZ-1/6W-5%"))
    )
    (comp (ref "R31")
      (value "10k")
      (footprint "eagle-import:AXIAL-0.3")
      (libsource (lib "eagle-import") (part "10KOHM-HORIZ-1/6W-5%"))
    )
    (comp (ref "R32")
      (value "10k")
      (footprint "eagle-import:AXIAL-0.3")
      (libsource (lib "eagle-import") (part "10KOHM-HORIZ-1/6W-5%"))
    )
    (comp (ref "R33")
      (value "10k")
      (footprint "eagle-import:AXIAL-0.3")
      (libsource (lib "eagle-import") (part "10KOHM-HORIZ-1/6W-5%"))
    )
    (comp (ref "R34")
      (value "10k")
      (footprint "eagle-import:AXIAL-0.3")
      (libsource (lib "eagle-import") (part "10KOHM-HORIZ-1/6W-5%"))
    )
    (comp (ref "R35")
      (value "4.7k")
      (footprint "eagle-import:AXIAL-0.3")
      (libsource (lib "eagle-import") (part "10KOHM-HORIZ-1/4W-1%"))
    )
    (comp (ref "R36")
      (value "4.7k")
      (footprint "eagle-import:AXIAL-0.3")
      (libsource (lib "eagle-import") (part "10KOHM-HORIZ-1/4W-1%"))
    )
    (comp (ref "SCL")
      (value "2,15/1,0")
      (footprint "eagle-import:2,15_1,0")
      (libsource (lib "eagle-import") (part "2,15/1,0"))
    )
    (comp (ref "SCL1")
      (value "2,15/1,0")
      (footprint "eagle-import:2,15_1,0")
      (libsource (lib "eagle-import") (part "2,15/1,0"))
    )
    (comp (ref "SCL2")
      (value "2,15/1,0")
      (footprint "eagle-import:2,15_1,0")
      (libsource (lib "eagle-import") (part "2,15/1,0"))
    )
    (comp (ref "SCL3")
      (value "2,15/1,0")
      (footprint "eagle-import:2,15_1,0")
      (libsource (lib "eagle-import") (part "2,15/1,0"))
    )
    (comp (ref "SCL4")
      (value "2,15/1,0")
      (footprint "eagle-import:2,15_1,0")
      (libsource (lib "eagle-import") (part "2,15/1,0"))
    )
    (comp (ref "SCL5")
      (value "2,15/1,0")
      (footprint "eagle-import:2,15_1,0")
      (libsource (lib "eagle-import") (part "2,15/1,0"))
    )
    (comp (ref "SCL6")
      (value "2,15/1,0")
      (footprint "eagle-import:2,15_1,0")
      (libsource (lib "eagle-import") (part "2,15/1,0"))
    )
    (comp (ref "SCL7")
      (value "2,15/1,0")
      (footprint "eagle-import:2,15_1,0")
      (libsource (lib "eagle-import") (part "2,15/1,0"))
    )
    (comp (ref "SCL8")
      (value "2,15/1,0")
      (footprint "eagle-import:2,15_1,0")
      (libsource (lib "eagle-import") (part "2,15/1,0"))
    )
    (comp (ref "SCL9")
      (value "2,15/1,0")
      (footprint "eagle-import:2,15_1,0")
      (libsource (lib "eagle-import") (part "2,15/1,0"))
    )
    (comp (ref "SCL10")
      (value "2,15/1,0")
      (footprint "eagle-import:2,15_1,0")
      (libsource (lib "eagle-import") (part "2,15/1,0"))
    )
    (comp (ref "SCL11")
      (value "2,15/1,0")
      (footprint "eagle-import:2,15_1,0")
      (libsource (lib "eagle-import") (part "2,15/1,0"))
    )
    (comp (ref "SCL12")
      (value "2,15/1,0")
      (footprint "eagle-import:2,15_1,0")
      (libsource (lib "eagle-import") (part "2,15/1,0"))
    )
    (comp (ref "SCL13")
      (value "2,15/1,0")
      (footprint "eagle-import:2,15_1,0")
      (libsource (lib "eagle-import") (part "2,15/1,0"))
    )
    (comp (ref "SCL14")
      (value "2,15/1,0")
      (footprint "eagle-import:2,15_1,0")
      (libsource (lib "eagle-import") (part "2,15/1,0"))
    )
    (comp (ref "SCL15")
      (value "2,15/1,0")
      (footprint "eagle-import:2,15_1,0")
      (libsource (lib "eagle-import") (part "2,15/1,0"))
    )
    (comp (ref "SCL16")
      (value "2,15/1,0")
      (footprint "eagle-import:2,15_1,0")
      (libsource (lib "eagle-import") (part "2,15/1,0"))
    )
    (comp (ref "SCL17")
      (value "2,15/1,0")
      (footprint "eagle-import:2,15_1,0")
      (libsource (lib "eagle-import") (part "2,15/1,0"))
    )
    (comp (ref "SCL18")
      (value "2,15/1,0")
      (footprint "eagle-import:2,15_1,0")
      (libsource (lib "eagle-import") (part "2,15/1,0"))
    )
    (comp (ref "SCL19")
      (value "2,15/1,0")
      (footprint "eagle-import:2,15_1,0")
      (libsource (lib "eagle-import") (part "2,15/1,0"))
    )
    (comp (ref "SCL20")
      (value "2,15/1,0")
      (footprint "eagle-import:2,15_1,0")
      (libsource (lib "eagle-import") (part "2,15/1,0"))
    )
    (comp (ref "SCL21")
      (value "2,15/1,0")
      (footprint "eagle-import:2,15_1,0")
      (libsource (lib "eagle-import") (part "2,15/1,0"))
    )
    (comp (ref "SCL22")
      (value "2,15/1,0")
      (footprint "eagle-import:2,15_1,0")
      (libsource (lib "eagle-import") (part "2,15/1,0"))
    )
    (comp (ref "SCL23")
      (value "2,15/1,0")
      (footprint "eagle-import:2,15_1,0")
      (libsource (lib "eagle-import") (part "2,15/1,0"))
    )
    (comp (ref "SCL24")
      (value "2,15/1,0")
      (footprint "eagle-import:2,15_1,0")
      (libsource (lib "eagle-import") (part "2,15/1,0"))
    )
    (comp (ref "SDA")
      (value "2,15/1,0")
      (footprint "eagle-import:2,15_1,0")
      (libsource (lib "eagle-import") (part "2,15/1,0"))
    )
    (comp (ref "SDA1")
      (value "2,15/1,0")
      (footprint "eagle-import:2,15_1,0")
      (libsource (lib "eagle-import") (part "2,15/1,0"))
    )
    (comp (ref "SDA2")
      (value "2,15/1,0")
      (footprint "eagle-import:2,15_1,0")
      (libsource (lib "eagle-import") (part "2,15/1,0"))
    )
    (comp (ref "SDA3")
      (value "2,15/1,0")
      (footprint "eagle-import:2,15_1,0")
      (libsource (lib "eagle-import") (part "2,15/1,0"))
    )
    (comp (ref "SDA4")
      (value "2,15/1,0")
      (footprint "eagle-import:2,15_1,0")
      (libsource (lib "eagle-import") (part "2,15/1,0"))
    )
    (comp (ref "SDA5")
      (value "2,15/1,0")
      (footprint "eagle-import:2,15_1,0")
      (libsource (lib "eagle-import") (part "2,15/1,0"))
    )
    (comp (ref "SDA6")
      (value "2,15/1,0")
      (footprint "eagle-import:2,15_1,0")
      (libsource (lib "eagle-import") (part "2,15/1,0"))
    )
    (comp (ref "SDA7")
      (value "2,15/1,0")
      (footprint "eagle-import:2,15_1,0")
      (libsource (lib "eagle-import") (part "2,15/1,0"))
    )
    (comp (ref "SDA8")
      (value "2,15/1,0")
      (footprint "eagle-import:2,15_1,0")
      (libsource (lib "eagle-import") (part "2,15/1,0"))
    )
    (comp (ref "SDA9")
      (value "2,15/1,0")
      (footprint "eagle-import:2,15_1,0")
      (libsource (lib "eagle-import") (part "2,15/1,0"))
    )
    (comp (ref "SDA10")
      (value "2,15/1,0")
      (footprint "eagle-import:2,15_1,0")
      (libsource (lib "eagle-import") (part "2,15/1,0"))
    )
    (comp (ref "SDA11")
      (value "2,15/1,0")
      (footprint "eagle-import:2,15_1,0")
      (libsource (lib "eagle-import") (part "2,15/1,0"))
    )
    (comp (ref "SDA12")
      (value "2,15/1,0")
      (footprint "eagle-import:2,15_1,0")
      (libsource (lib "eagle-import") (part "2,15/1,0"))
    )
    (comp (ref "SDA13")
      (value "2,15/1,0")
      (footprint "eagle-import:2,15_1,0")
      (libsource (lib "eagle-import") (part "2,15/1,0"))
    )
    (comp (ref "SDA14")
      (value "2,15/1,0")
      (footprint "eagle-import:2,15_1,0")
      (libsource (lib "eagle-import") (part "2,15/1,0"))
    )
    (comp (ref "SDA15")
      (value "2,15/1,0")
      (footprint "eagle-import:2,15_1,0")
      (libsource (lib "eagle-import") (part "2,15/1,0"))
    )
    (comp (ref "SDA16")
      (value "2,15/1,0")
      (footprint "eagle-import:2,15_1,0")
      (libsource (lib "eagle-import") (part "2,15/1,0"))
    )
    (comp (ref "SDA17")
      (value "2,15/1,0")
      (footprint "eagle-import:2,15_1,0")
      (libsource (lib "eagle-import") (part "2,15/1,0"))
    )
    (comp (ref "SDA18")
      (value "2,15/1,0")
      (footprint "eagle-import:2,15_1,0")
      (libsource (lib "eagle-import") (part "2,15/1,0"))
    )
    (comp (ref "SDA19")
      (value "2,15/1,0")
      (footprint "eagle-import:2,15_1,0")
      (libsource (lib "eagle-import") (part "2,15/1,0"))
    )
    (comp (ref "SDA20")
      (value "2,15/1,0")
      (footprint "eagle-import:2,15_1,0")
      (libsource (lib "eagle-import") (part "2,15/1,0"))
    )
    (comp (ref "SDA21")
      (value "2,15/1,0")
      (footprint "eagle-import:2,15_1,0")
      (libsource (lib "eagle-import") (part "2,15/1,0"))
    )
    (comp (ref "SDA22")
      (value "2,15/1,0")
      (footprint "eagle-import:2,15_1,0")
      (libsource (lib "eagle-import") (part "2,15/1,0"))
    )
    (comp (ref "SDA23")
      (value "2,15/1,0")
      (footprint "eagle-import:2,15_1,0")
      (libsource (lib "eagle-import") (part "2,15/1,0"))
    )
    (comp (ref "SDA24")
      (value "2,15/1,0")
      (footprint "eagle-import:2,15_1,0")
      (libsource (lib "eagle-import") (part "2,15/1,0"))
    )
    (comp (ref "VCC")
      (value "2,15/1,0")
      (footprint "eagle-import:2,15_1,0")
      (libsource (lib "eagle-import") (part "2,15/1,0"))
    )
    (comp (ref "VCC1")
      (value "2,15/1,0")
      (footprint "eagle-import:2,15_1,0")
      (libsource (lib "eagle-import") (part "2,15/1,0"))
    )
    (comp (ref "VCC2")
      (value "2,15/1,0")
      (footprint "eagle-import:2,15_1,0")
      (libsource (lib "eagle-import") (part "2,15/1,0"))
    )
    (comp (ref "VCC3")
      (value "2,15/1,0")
      (footprint "eagle-import:2,15_1,0")
      (libsource (lib "eagle-import") (part "2,15/1,0"))
    )
    (comp (ref "VCC4")
      (value "2,15/1,0")
      (footprint "eagle-import:2,15_1,0")
      (libsource (lib "eagle-import") (part "2,15/1,0"))
    )
    (comp (ref "VCC5")
      (value "2,15/1,0")
      (footprint "eagle-import:2,15_1,0")
      (libsource (lib "eagle-import") (part "2,15/1,0"))
    )
    (comp (ref "VCC6")
      (value "2,15/1,0")
      (footprint "eagle-import:2,15_1,0")
      (libsource (lib "eagle-import") (part "2,15/1,0"))
    )
    (comp (ref "VCC7")
      (value "2,15/1,0")
      (footprint "eagle-import:2,15_1,0")
      (libsource (lib "eagle-import") (part "2,15/1,0"))
    )
    (comp (ref "VCC8")
      (value "2,15/1,0")
      (footprint "eagle-import:2,15_1,0")
      (libsource (lib "eagle-import") (part "2,15/1,0"))
    )
    (comp (ref "VCC9")
      (value "2,15/1,0")
      (footprint "eagle-import:2,15_1,0")
      (libsource (lib "eagle-import") (part "2,15/1,0"))
    )
    (comp (ref "VCC10")
      (value "2,15/1,0")
      (footprint "eagle-import:2,15_1,0")
      (libsource (lib "eagle-import") (part "2,15/1,0"))
    )
    (comp (ref "VCC11")
      (value "2,15/1,0")
      (footprint "eagle-import:2,15_1,0")
      (libsource (lib "eagle-import") (part "2,15/1,0"))
    )
    (comp (ref "VCC12")
      (value "2,15/1,0")
      (footprint "eagle-import:2,15_1,0")
      (libsource (lib "eagle-import") (part "2,15/1,0"))
    )
    (comp (ref "VCC13")
      (value "2,15/1,0")
      (footprint "eagle-import:2,15_1,0")
      (libsource (lib "eagle-import") (part "2,15/1,0"))
    )
    (comp (ref "VCC14")
      (value "2,15/1,0")
      (footprint "eagle-import:2,15_1,0")
      (libsource (lib "eagle-import") (part "2,15/1,0"))
    )
    (comp (ref "VCC15")
      (value "2,15/1,0")
      (footprint "eagle-import:2,15_1,0")
      (libsource (lib "eagle-import") (part "2,15/1,0"))
    )
    (comp (ref "VCC16")
      (value "2,15/1,0")
      (footprint "eagle-import:2,15_1,0")
      (libsource (lib "eagle-import") (part "2,15/1,0"))
    )
    (comp (ref "VCC17")
      (value "2,15/1,0")
      (footprint "eagle-import:2,15_1,0")
      (libsource (lib "eagle-import") (part "2,15/1,0"))
    )
    (comp (ref "VCC18")
      (value "2,15/1,0")
      (footprint "eagle-import:2,15_1,0")
      (libsource (lib "eagle-import") (part "2,15/1,0"))
    )
    (comp (ref "VCC19")
      (value "2,15/1,0")
      (footprint "eagle-import:2,15_1,0")
      (libsource (lib "eagle-import") (part "2,15/1,0"))
    )
    (comp (ref "VCC20")
      (value "2,15/1,0")
      (footprint "eagle-import:2,15_1,0")
      (libsource (lib "eagle-import") (part "2,15/1,0"))
    )
    (comp (ref "VCC21")
      (value "2,15/1,0")
      (footprint "eagle-import:2,15_1,0")
      (libsource (lib "eagle-import") (part "2,15/1,0"))
    )
    (comp (ref "VCC22")
      (value "2,15/1,0")
      (footprint "eagle-import:2,15_1,0")
      (libsource (lib "eagle-import") (part "2,15/1,0"))
    )
    (comp (ref "VCC23")
      (value "2,15/1,0")
      (footprint "eagle-import:2,15_1,0")
      (libsource (lib "eagle-import") (part "2,15/1,0"))
    )
    (comp (ref "VCC24")
      (value "2,15/1,0")
      (footprint "eagle-import:2,15_1,0")
      (libsource (lib "eagle-import") (part "2,15/1,0"))
    )
  )
  (nets
    (net (code "1") (name "5V") (class "Default")
      (node (ref "ARD-5V") (pin "1") (pinfunction "P_1") (pintype "passive"))
      (node (ref "IC1") (pin "18") (pinfunction "VCC_18") (pintype "power_in"))
      (node (ref "IC1") (pin "3") (pinfunction "A2_3") (pintype "input"))
      (node (ref "IC1") (pin "6") (pinfunction "/RST_6") (pintype "input"))
      (node (ref "IC2") (pin "18") (pinfunction "VCC_18") (pintype "power_in"))
      (node (ref "IC2") (pin "4") (pinfunction "A1_4") (pintype "input"))
      (node (ref "IC2") (pin "6") (pinfunction "/RST_6") (pintype "input"))
      (node (ref "IC3") (pin "18") (pinfunction "VCC_18") (pintype "power_in"))
      (node (ref "IC3") (pin "5") (pinfunction "A0_5") (pintype "input"))
      (node (ref "IC3") (pin "6") (pinfunction "/RST_6") (pintype "input"))
      (node (ref "J1") (pin "3") (pinfunction "3_3") (pintype "passive"))
      (node (ref "J10") (pin "3") (pinfunction "3_3") (pintype "passive"))
      (node (ref "J11") (pin "3") (pinfunction "3_3") (pintype "passive"))
      (node (ref "J12") (pin "3") (pinfunction "3_3") (pintype "passive"))
      (node (ref "J13") (pin "3") (pinfunction "3_3") (pintype "passive"))
      (node (ref "J14") (pin "3") (pinfunction "3_3") (pintype "passive"))
      (node (ref "J15") (pin "3") (pinfunction "3_3") (pintype "passive"))
      (node (ref "J16") (pin "3") (pinfunction "3_3") (pintype "passive"))
      (node (ref "J17") (pin "3") (pinfunction "3_3") (pintype "passive"))
      (node (ref "J18") (pin "3") (pinfunction "3_3") (pintype "passive"))
      (node (ref "J19") (pin "3") (pinfunction "3_3") (pintype "passive"))
      (node (ref "J2") (pin "3") (pinfunction "3_3") (pintype "passive"))
      (node (ref "J20") (pin "3") (pinfunction "3_3") (pintype "passive"))
      (node (ref "J21") (pin "3") (pinfunction "3_3") (pintype "passive"))
      (node (ref "J22") (pin "3") (pinfunction "3_3") (pintype "passive"))
      (node (ref "J23") (pin "3") (pinfunction "3_3") (pintype "passive"))
      (node (ref "J24") (pin "3") (pinfunction "3_3") (pintype "passive"))
      (node (ref "J25") (pin "3") (pinfunction "3_3") (pintype "passive"))
      (node (ref "J3") (pin "3") (pinfunction "3_3") (pintype "passive"))
      (node (ref "J4") (pin "3") (pinfunction "3_3") (pintype "passive"))
      (node (ref "J5") (pin "3") (pinfunction "3_3") (pintype "passive"))
      (node (ref "J6") (pin "3") (pinfunction "3_3") (pintype "passive"))
      (node (ref "J7") (pin "3") (pinfunction "3_3") (pintype "passive"))
      (node (ref "J8") (pin "3") (pinfunction "3_3") (pintype "passive"))
      (node (ref "J9") (pin "3") (pinfunction "3_3") (pintype "passive"))
      (node (ref "R1") (pin "P$1") (pinfunction "1_P$1") (pintype "passive"))
      (node (ref "R10") (pin "P$2") (pinfunction "2_P$2") (pintype "passive"))
      (node (ref "R2") (pin "P$1") (pinfunction "1_P$1") (pintype "passive"))
      (node (ref "R3") (pin "P$1") (pinfunction "1_P$1") (pintype "passive"))
      (node (ref "R35") (pin "P$2") (pinfunction "2_P$2") (pintype "passive"))
      (node (ref "R36") (pin "P$1") (pinfunction "1_P$1") (pintype "passive"))
      (node (ref "R4") (pin "P$1") (pinfunction "1_P$1") (pintype "passive"))
      (node (ref "R5") (pin "P$1") (pinfunction "1_P$1") (pintype "passive"))
      (node (ref "R6") (pin "P$2") (pinfunction "2_P$2") (pintype "passive"))
      (node (ref "R7") (pin "P$2") (pinfunction "2_P$2") (pintype "passive"))
      (node (ref "R8") (pin "P$2") (pinfunction "2_P$2") (pintype "passive"))
      (node (ref "R9") (pin "P$2") (pinfunction "2_P$2") (pintype "passive"))
    )
    (net (code "2") (name "GND") (class "Default")
      (node (ref "ARD-GND") (pin "1") (pinfunction "P_1") (pintype "passive"))
      (node (ref "DECOUP-CAP") (pin "P$2") (pinfunction "2_P$2") (pintype "passive"))
      (node (ref "GND") (pin "1") (pinfunction "P_1") (pintype "passive"))
      (node (ref "GND1") (pin "1") (pinfunction "P_1") (pintype "passive"))
      (node (ref "GND10") (pin "1") (pinfunction "P_1") (pintype "passive"))
      (node (ref "GND11") (pin "1") (pinfunction "P_1") (pintype "passive"))
      (node (ref "GND12") (pin "1") (pinfunction "P_1") (pintype "passive"))
      (node (ref "GND13") (pin "1") (pinfunction "P_1") (pintype "passive"))
      (node (ref "GND14") (pin "1") (pinfunction "P_1") (pintype "passive"))
      (node (ref "GND15") (pin "1") (pinfunction "P_1") (pintype "passive"))
      (node (ref "GND16") (pin "1") (pinfunction "P_1") (pintype "passive"))
      (node (ref "GND17") (pin "1") (pinfunction "P_1") (pintype "passive"))
      (node (ref "GND18") (pin "1") (pinfunction "P_1") (pintype "passive"))
      (node (ref "GND19") (pin "1") (pinfunction "P_1") (pintype "passive"))
      (node (ref "GND2") (pin "1") (pinfunction "P_1") (pintype "passive"))
      (node (ref "GND20") (pin "1") (pinfunction "P_1") (pintype "passive"))
      (node (ref "GND21") (pin "1") (pinfunction "P_1") (pintype "passive"))
      (node (ref "GND22") (pin "1") (pinfunction "P_1") (pintype "passive"))
      (node (ref "GND23") (pin "1") (pinfunction "P_1") (pintype "passive"))
      (node (ref "GND24") (pin "1") (pinfunction "P_1") (pintype "passive"))
      (node (ref "GND3") (pin "1") (pinfunction "P_1") (pintype "passive"))
      (node (ref "GND4") (pin "1") (pinfunction "P_1") (pintype "passive"))
      (node (ref "GND5") (pin "1") (pinfunction "P_1") (pintype "passive"))
      (node (ref "GND6") (pin "1") (pinfunction "P_1") (pintype "passive"))
      (node (ref "GND7") (pin "1") (pinfunction "P_1") (pintype "passive"))
      (node (ref "GND8") (pin "1") (pinfunction "P_1") (pintype "passive"))
      (node (ref "GND9") (pin "1") (pinfunction "P_1") (pintype "passive"))
      (node (ref "IC1") (pin "4") (pinfunction "A1_4") (pintype "input"))
      (node (ref "IC1") (pin "5") (pinfunction "A0_5") (pintype "input"))
      (node (ref "IC1") (pin "9") (pinfunction "GND_9") (pintype "power_in"))
      (node (ref "IC2") (pin "3") (pinfunction "A2_3") (pintype "input"))
      (node (ref "IC2") (pin "5") (pinfunction "A0_5") (pintype "input"))
      (node (ref "IC2") (pin "9") (pinfunction "GND_9") (pintype "power_in"))
      (node (ref "IC3") (pin "3") (pinfunction "A2_3") (pintype "input"))
      (node (ref "IC3") (pin "4") (pinfunction "A1_4") (pintype "input"))
      (node (ref "IC3") (pin "9") (pinfunction "GND_9") (pintype "power_in"))
      (node (ref "J1") (pin "2") (pinfunction "2_2") (pintype "passive"))
      (node (ref "J10") (pin "2") (pinfunction "2_2") (pintype "passive"))
      (node (ref "J11") (pin "2") (pinfunction "2_2") (pintype "passive"))
      (node (ref "J12") (pin "2") (pinfunction "2_2") (pintype "passive"))
      (node (ref "J13") (pin "2") (pinfunction "2_2") (pintype "passive"))
      (node (ref "J14") (pin "2") (pinfunction "2_2") (pintype "passive"))
      (node (ref "J15") (pin "2") (pinfunction "2_2") (pintype "passive"))
      (node (ref "J16") (pin "2") (pinfunction "2_2") (pintype "passive"))
      (node (ref "J17") (pin "2") (pinfunction "2_2") (pintype "passive"))
      (node (ref "J18") (pin "2") (pinfunction "2_2") (pintype "passive"))
      (node (ref "J19") (pin "2") (pinfunction "2_2") (pintype "passive"))
      (node (ref "J2") (pin "2") (pinfunction "2_2") (pintype "passive"))
      (node (ref "J20") (pin "2") (pinfunction "2_2") (pintype "passive"))
      (node (ref "J21") (pin "2") (pinfunction "2_2") (pintype "passive"))
      (node (ref "J22") (pin "2") (pinfunction "2_2") (pintype "passive"))
      (node (ref "J23") (pin "2") (pinfunction "2_2") (pintype "passive"))
      (node (ref "J24") (pin "2") (pinfunction "2_2") (pintype "passive"))
      (node (ref "J25") (pin "2") (pinfunction "2_2") (pintype "passive"))
      (node (ref "J3") (pin "2") (pinfunction "2_2") (pintype "passive"))
      (node (ref "J4") (pin "2") (pinfunction "2_2") (pintype "passive"))
      (node (ref "J5") (pin "2") (pinfunction "2_2") (pintype "passive"))
      (node (ref "J6") (pin "2") (pinfunction "2_2") (pintype "passive"))
      (node (ref "J7") (pin "2") (pinfunction "2_2") (pintype "passive"))
      (node (ref "J8") (pin "2") (pinfunction "2_2") (pintype "passive"))
      (node (ref "J9") (pin "2") (pinfunction "2_2") (pintype "passive"))
      (node (ref "PAD11") (pin "1") (pinfunction "P_1") (pintype "passive"))
      (node (ref "PAD15") (pin "1") (pinfunction "P_1") (pintype "passive"))
      (node (ref "PAD19") (pin "1") (pinfunction "P_1") (pintype "passive"))
      (node (ref "PAD23") (pin "1") (pinfunction "P_1") (pintype "passive"))
      (node (ref "PAD27") (pin "1") (pinfunction "P_1") (pintype "passive"))
      (node (ref "PAD3") (pin "1") (pinfunction "P_1") (pintype "passive"))
      (node (ref "PAD31") (pin "1") (pinfunction "P_1") (pintype "passive"))
      (node (ref "PAD35") (pin "1") (pinfunction "P_1") (pintype "passive"))
      (node (ref "PAD39") (pin "1") (pinfunction "P_1") (pintype "passive"))
      (node (ref "PAD43") (pin "1") (pinfunction "P_1") (pintype "passive"))
      (node (ref "PAD47") (pin "1") (pinfunction "P_1") (pintype "passive"))
      (node (ref "PAD51") (pin "1") (pinfunction "P_1") (pintype "passive"))
      (node (ref "PAD55") (pin "1") (pinfunction "P_1") (pintype "passive"))
      (node (ref "PAD59") (pin "1") (pinfunction "P_1") (pintype "passive"))
      (node (ref "PAD63") (pin "1") (pinfunction "P_1") (pintype "passive"))
      (node (ref "PAD67") (pin "1") (pinfunction "P_1") (pintype "passive"))
      (node (ref "PAD7") (pin "1") (pinfunction "P_1") (pintype "passive"))
      (node (ref "PAD71") (pin "1") (pinfunction "P_1") (pintype "passive"))
      (node (ref "PAD75") (pin "1") (pinfunction "P_1") (pintype "passive"))
      (node (ref "PAD79") (pin "1") (pinfunction "P_1") (pintype "passive"))
      (node (ref "PAD83") (pin "1") (pinfunction "P_1") (pintype "passive"))
      (node (ref "PAD87") (pin "1") (pinfunction "P_1") (pintype "passive"))
      (node (ref "PAD91") (pin "1") (pinfunction "P_1") (pintype "passive"))
      (node (ref "PAD95") (pin "1") (pinfunction "P_1") (pintype "passive"))
      (node (ref "PAD99") (pin "1") (pinfunction "P_1") (pintype "passive"))
    )
    (net (code "3") (name "GPIO1") (class "Default")
      (node (ref "J1") (pin "1") (pinfunction "1_1") (pintype "passive"))
      (node (ref "R27") (pin "P$2") (pinfunction "2_P$2") (pintype "passive"))
    )
    (net (code "4") (name "GPIO2") (class "Default")
      (node (ref "J2") (pin "1") (pinfunction "1_1") (pintype "passive"))
      (node (ref "R28") (pin "P$2") (pinfunction "2_P$2") (pintype "passive"))
    )
    (net (code "5") (name "GPIO3") (class "Default")
      (node (ref "J3") (pin "1") (pinfunction "1_1") (pintype "passive"))
      (node (ref "R29") (pin "P$2") (pinfunction "2_P$2") (pintype "passive"))
    )
    (net (code "6") (name "GPIO4") (class "Default")
      (node (ref "J4") (pin "1") (pinfunction "1_1") (pintype "passive"))
      (node (ref "R30") (pin "P$2") (pinfunction "2_P$2") (pintype "passive"))
    )
    (net (code "7") (name "GPIO5") (class "Default")
      (node (ref "J5") (pin "1") (pinfunction "1_1") (pintype "passive"))
      (node (ref "R31") (pin "P$2") (pinfunction "2_P$2") (pintype "passive"))
    )
    (net (code "8") (name "GPIO6") (class "Default")
      (node (ref "J6") (pin "1") (pinfunction "1_1") (pintype "passive"))
      (node (ref "R33") (pin "P$2") (pinfunction "2_P$2") (pintype "passive"))
    )
    (net (code "9") (name "GPIO7") (class "Default")
      (node (ref "J7") (pin "1") (pinfunction "1_1") (pintype "passive"))
      (node (ref "R32") (pin "P$2") (pinfunction "2_P$2") (pintype "passive"))
    )
    (net (code "10") (name "GPIO8") (class "Default")
      (node (ref "J8") (pin "1") (pinfunction "1_1") (pintype "passive"))
      (node (ref "R34") (pin "P$2") (pinfunction "2_P$2") (pintype "passive"))
    )
    (net (code "11") (name "GPIO9") (class "Default")
      (node (ref "J9") (pin "1") (pinfunction "1_1") (pintype "passive"))
      (node (ref "R11") (pin "P$2") (pinfunction "2_P$2") (pintype "passive"))
    )
    (net (code "12") (name "GPIO10") (class "Default")
      (node (ref "J10") (pin "1") (pinfunction "1_1") (pintype "passive"))
      (node (ref "R12") (pin "P$2") (pinfunction "2_P$2") (pintype "passive"))
    )
    (net (code "13") (name "GPIO11") (class "Default")
      (node (ref "J11") (pin "1") (pinfunction "1_1") (pintype "passive"))
      (node (ref "R13") (pin "P$2") (pinfunction "2_P$2") (pintype "passive"))
    )
    (net (code "14") (name "GPIO12") (class "Default")
      (node (ref "J12") (pin "1") (pinfunction "1_1") (pintype "passive"))
      (node (ref "R14") (pin "P$2") (pinfunction "2_P$2") (pintype "passive"))
    )
    (net (code "15") (name "GPIO13") (class "Default")
      (node (ref "J13") (pin "1") (pinfunction "1_1") (pintype "passive"))
      (node (ref "R15") (pin "P$2") (pinfunction "2_P$2") (pintype "passive"))
    )
    (net (code "16") (name "GPIO14") (class "Default")
      (node (ref "J14") (pin "1") (pinfunction "1_1") (pintype "passive"))
      (node (ref "R16") (pin "P$2") (pinfunction "2_P$2") (pintype "passive"))
    )
    (net (code "17") (name "GPIO15") (class "Default")
      (node (ref "J15") (pin "1") (pinfunction "1_1") (pintype "passive"))
      (node (ref "R17") (pin "P$2") (pinfunction "2_P$2") (pintype "passive"))
    )
    (net (code "18") (name "GPIO16") (class "Default")
      (node (ref "J16") (pin "1") (pinfunction "1_1") (pintype "passive"))
      (node (ref "R18") (pin "P$2") (pinfunction "2_P$2") (pintype "passive"))
    )
    (net (code "19") (name "GPIO17") (class "Default")
      (node (ref "J17") (pin "1") (pinfunction "1_1") (pintype "passive"))
      (node (ref "R19") (pin "P$2") (pinfunction "2_P$2") (pintype "passive"))
    )
    (net (code "20") (name "GPIO18") (class "Default")
      (node (ref "J18") (pin "1") (pinfunction "1_1") (pintype "passive"))
      (node (ref "R20") (pin "P$2") (pinfunction "2_P$2") (pintype "passive"))
    )
    (net (code "21") (name "GPIO19") (class "Default")
      (node (ref "J19") (pin "1") (pinfunction "1_1") (pintype "passive"))
      (node (ref "R21") (pin "P$2") (pinfunction "2_P$2") (pintype "passive"))
    )
    (net (code "22") (name "GPIO20") (class "Default")
      (node (ref "J20") (pin "1") (pinfunction "1_1") (pintype "passive"))
      (node (ref "R22") (pin "P$2") (pinfunction "2_P$2") (pintype "passive"))
    )
    (net (code "23") (name "GPIO21") (class "Default")
      (node (ref "J21") (pin "1") (pinfunction "1_1") (pintype "passive"))
      (node (ref "R23") (pin "P$2") (pinfunction "2_P$2") (pintype "passive"))
    )
    (net (code "24") (name "GPIO22") (class "Default")
      (node (ref "J22") (pin "1") (pinfunction "1_1") (pintype "passive"))
      (node (ref "R24") (pin "P$2") (pinfunction "2_P$2") (pintype "passive"))
    )
    (net (code "25") (name "GPIO23") (class "Default")
      (node (ref "J23") (pin "1") (pinfunction "1_1") (pintype "passive"))
      (node (ref "R25") (pin "P$2") (pinfunction "2_P$2") (pintype "passive"))
    )
    (net (code "26") (name "GPIO24") (class "Default")
      (node (ref "J24") (pin "1") (pinfunction "1_1") (pintype "passive"))
      (node (ref "R26") (pin "P$2") (pinfunction "2_P$2") (pintype "passive"))
    )
    (net (code "27") (name "GPIO25") (class "Default")
      (node (ref "ARD-DIG-PIN") (pin "1") (pinfunction "P_1") (pintype "passive"))
      (node (ref "J25") (pin "1") (pinfunction "1_1") (pintype "passive"))
    )
    (net (code "28") (name "N$2") (class "Default")
      (node (ref "IC1") (pin "8") (pinfunction "INT_8") (pintype "output"))
    )
    (net (code "29") (name "N$29") (class "Default")
      (node (ref "IC2") (pin "8") (pinfunction "INT_8") (pintype "output"))
    )
    (net (code "30") (name "N$36") (class "Default")
      (node (ref "IC3") (pin "8") (pinfunction "INT_8") (pintype "output"))
    )
    (net (code "31") (name "Net-(IC1-GP0)") (class "Default")
      (node (ref "IC1") (pin "10") (pinfunction "GP0_10") (pintype "bidirectional"))
      (node (ref "R27") (pin "P$1") (pinfunction "1_P$1") (pintype "passive"))
    )
    (net (code "32") (name "Net-(IC1-GP1)") (class "Default")
      (node (ref "IC1") (pin "11") (pinfunction "GP1_11") (pintype "bidirectional"))
      (node (ref "R28") (pin "P$1") (pinfunction "1_P$1") (pintype "passive"))
    )
    (net (code "33") (name "Net-(IC1-GP2)") (class "Default")
      (node (ref "IC1") (pin "12") (pinfunction "GP2_12") (pintype "bidirectional"))
      (node (ref "R29") (pin "P$1") (pinfunction "1_P$1") (pintype "passive"))
    )
    (net (code "34") (name "Net-(IC1-GP3)") (class "Default")
      (node (ref "IC1") (pin "13") (pinfunction "GP3_13") (pintype "bidirectional"))
      (node (ref "R30") (pin "P$1") (pinfunction "1_P$1") (pintype "passive"))
    )
    (net (code "35") (name "Net-(IC1-GP4)") (class "Default")
      (node (ref "IC1") (pin "14") (pinfunction "GP4_14") (pintype "bidirectional"))
      (node (ref "R31") (pin "P$1") (pinfunction "1_P$1") (pintype "passive"))
    )
    (net (code "36") (name "Net-(IC1-GP5)") (class "Default")
      (node (ref "IC1") (pin "15") (pinfunction "GP5_15") (pintype "bidirectional"))
      (node (ref "R33") (pin "P$1") (pinfunction "1_P$1") (pintype "passive"))
    )
    (net (code "37") (name "Net-(IC1-GP6)") (class "Default")
      (node (ref "IC1") (pin "16") (pinfunction "GP6_16") (pintype "bidirectional"))
      (node (ref "R32") (pin "P$1") (pinfunction "1_P$1") (pintype "passive"))
    )
    (net (code "38") (name "Net-(IC1-GP7)") (class "Default")
      (node (ref "IC1") (pin "17") (pinfunction "GP7_17") (pintype "bidirectional"))
      (node (ref "R34") (pin "P$1") (pinfunction "1_P$1") (pintype "passive"))
    )
    (net (code "39") (name "Net-(IC2-GP0)") (class "Default")
      (node (ref "IC2") (pin "10") (pinfunction "GP0_10") (pintype "bidirectional"))
      (node (ref "R11") (pin "P$1") (pinfunction "1_P$1") (pintype "passive"))
    )
    (net (code "40") (name "Net-(IC2-GP1)") (class "Default")
      (node (ref "IC2") (pin "11") (pinfunction "GP1_11") (pintype "bidirectional"))
      (node (ref "R12") (pin "P$1") (pinfunction "1_P$1") (pintype "passive"))
    )
    (net (code "41") (name "Net-(IC2-GP2)") (class "Default")
      (node (ref "IC2") (pin "12") (pinfunction "GP2_12") (pintype "bidirectional"))
      (node (ref "R13") (pin "P$1") (pinfunction "1_P$1") (pintype "passive"))
    )
    (net (code "42") (name "Net-(IC2-GP3)") (class "Default")
      (node (ref "IC2") (pin "13") (pinfunction "GP3_13") (pintype "bidirectional"))
      (node (ref "R14") (pin "P$1") (pinfunction "1_P$1") (pintype "passive"))
    )
    (net (code "43") (name "Net-(IC2-GP4)") (class "Default")
      (node (ref "IC2") (pin "14") (pinfunction "GP4_14") (pintype "bidirectional"))
      (node (ref "R15") (pin "P$1") (pinfunction "1_P$1") (pintype "passive"))
    )
    (net (code "44") (name "Net-(IC2-GP5)") (class "Default")
      (node (ref "IC2") (pin "15") (pinfunction "GP5_15") (pintype "bidirectional"))
      (node (ref "R16") (pin "P$1") (pinfunction "1_P$1") (pintype "passive"))
    )
    (net (code "45") (name "Net-(IC2-GP6)") (class "Default")
      (node (ref "IC2") (pin "16") (pinfunction "GP6_16") (pintype "bidirectional"))
      (node (ref "R17") (pin "P$1") (pinfunction "1_P$1") (pintype "passive"))
    )
    (net (code "46") (name "Net-(IC2-GP7)") (class "Default")
      (node (ref "IC2") (pin "17") (pinfunction "GP7_17") (pintype "bidirectional"))
      (node (ref "R18") (pin "P$1") (pinfunction "1_P$1") (pintype "passive"))
    )
    (net (code "47") (name "Net-(IC3-GP0)") (class "Default")
      (node (ref "IC3") (pin "10") (pinfunction "GP0_10") (pintype "bidirectional"))
      (node (ref "R19") (pin "P$1") (pinfunction "1_P$1") (pintype "passive"))
    )
    (net (code "48") (name "Net-(IC3-GP1)") (class "Default")
      (node (ref "IC3") (pin "11") (pinfunction "GP1_11") (pintype "bidirectional"))
      (node (ref "R20") (pin "P$1") (pinfunction "1_P$1") (pintype "passive"))
    )
    (net (code "49") (name "Net-(IC3-GP2)") (class "Default")
      (node (ref "IC3") (pin "12") (pinfunction "GP2_12") (pintype "bidirectional"))
      (node (ref "R21") (pin "P$1") (pinfunction "1_P$1") (pintype "passive"))
    )
    (net (code "50") (name "Net-(IC3-GP3)") (class "Default")
      (node (ref "IC3") (pin "13") (pinfunction "GP3_13") (pintype "bidirectional"))
      (node (ref "R22") (pin "P$1") (pinfunction "1_P$1") (pintype "passive"))
    )
    (net (code "51") (name "Net-(IC3-GP4)") (class "Default")
      (node (ref "IC3") (pin "14") (pinfunction "GP4_14") (pintype "bidirectional"))
      (node (ref "R23") (pin "P$1") (pinfunction "1_P$1") (pintype "passive"))
    )
    (net (code "52") (name "Net-(IC3-GP5)") (class "Default")
      (node (ref "IC3") (pin "15") (pinfunction "GP5_15") (pintype "bidirectional"))
      (node (ref "R24") (pin "P$1") (pinfunction "1_P$1") (pintype "passive"))
    )
    (net (code "53") (name "Net-(IC3-GP6)") (class "Default")
      (node (ref "IC3") (pin "16") (pinfunction "GP6_16") (pintype "bidirectional"))
      (node (ref "R25") (pin "P$1") (pinfunction "1_P$1") (pintype "passive"))
    )
    (net (code "54") (name "Net-(IC3-GP7)") (class "Default")
      (node (ref "IC3") (pin "17") (pinfunction "GP7_17") (pintype "bidirectional"))
      (node (ref "R26") (pin "P$1") (pinfunction "1_P$1") (pintype "passive"))
    )
    (net (code "55") (name "SCL") (class "Default")
      (node (ref "ARD-SCL") (pin "1") (pinfunction "P_1") (pintype "passive"))
      (node (ref "IC1") (pin "1") (pinfunction "SCL_1") (pintype "bidirectional"))
      (node (ref "IC2") (pin "1") (pinfunction "SCL_1") (pintype "bidirectional"))
      (node (ref "IC3") (pin "1") (pinfunction "SCL_1") (pintype "bidirectional"))
      (node (ref "PAD10") (pin "1") (pinfunction "P_1") (pintype "passive"))
      (node (ref "PAD14") (pin "1") (pinfunction "P_1") (pintype "passive"))
      (node (ref "PAD18") (pin "1") (pinfunction "P_1") (pintype "passive"))
      (node (ref "PAD2") (pin "1") (pinfunction "P_1") (pintype "passive"))
      (node (ref "PAD22") (pin "1") (pinfunction "P_1") (pintype "passive"))
      (node (ref "PAD26") (pin "1") (pinfunction "P_1") (pintype "passive"))
      (node (ref "PAD30") (pin "1") (pinfunction "P_1") (pintype "passive"))
      (node (ref "PAD34") (pin "1") (pinfunction "P_1") (pintype "passive"))
      (node (ref "PAD38") (pin "1") (pinfunction "P_1") (pintype "passive"))
      (node (ref "PAD42") (pin "1") (pinfunction "P_1") (pintype "passive"))
      (node (ref "PAD46") (pin "1") (pinfunction "P_1") (pintype "passive"))
      (node (ref "PAD50") (pin "1") (pinfunction "P_1") (pintype "passive"))
      (node (ref "PAD54") (pin "1") (pinfunction "P_1") (pintype "passive"))
      (node (ref "PAD58") (pin "1") (pinfunction "P_1") (pintype "passive"))
      (node (ref "PAD6") (pin "1") (pinfunction "P_1") (pintype "passive"))
      (node (ref "PAD62") (pin "1") (pinfunction "P_1") (pintype "passive"))
      (node (ref "PAD66") (pin "1") (pinfunction "P_1") (pintype "passive"))
      (node (ref "PAD70") (pin "1") (pinfunction "P_1") (pintype "passive"))
      (node (ref "PAD74") (pin "1") (pinfunction "P_1") (pintype "passive"))
      (node (ref "PAD78") (pin "1") (pinfunction "P_1") (pintype "passive"))
      (node (ref "PAD82") (pin "1") (pinfunction "P_1") (pintype "passive"))
      (node (ref "PAD86") (pin "1") (pinfunction "P_1") (pintype "passive"))
      (node (ref "PAD90") (pin "1") (pinfunction "P_1") (pintype "passive"))
      (node (ref "PAD94") (pin "1") (pinfunction "P_1") (pintype "passive"))
      (node (ref "PAD98") (pin "1") (pinfunction "P_1") (pintype "passive"))
      (node (ref "R1") (pin "P$2") (pinfunction "2_P$2") (pintype "passive"))
      (node (ref "R2") (pin "P$2") (pinfunction "2_P$2") (pintype "passive"))
      (node (ref "R3") (pin "P$2") (pinfunction "2_P$2") (pintype "passive"))
      (node (ref "R36") (pin "P$2") (pinfunction "2_P$2") (pintype "passive"))
      (node (ref "R4") (pin "P$2") (pinfunction "2_P$2") (pintype "passive"))
      (node (ref "R5") (pin "P$2") (pinfunction "2_P$2") (pintype "passive"))
      (node (ref "SCL") (pin "1") (pinfunction "P_1") (pintype "passive"))
      (node (ref "SCL1") (pin "1") (pinfunction "P_1") (pintype "passive"))
      (node (ref "SCL10") (pin "1") (pinfunction "P_1") (pintype "passive"))
      (node (ref "SCL11") (pin "1") (pinfunction "P_1") (pintype "passive"))
      (node (ref "SCL12") (pin "1") (pinfunction "P_1") (pintype "passive"))
      (node (ref "SCL13") (pin "1") (pinfunction "P_1") (pintype "passive"))
      (node (ref "SCL14") (pin "1") (pinfunction "P_1") (pintype "passive"))
      (node (ref "SCL15") (pin "1") (pinfunction "P_1") (pintype "passive"))
      (node (ref "SCL16") (pin "1") (pinfunction "P_1") (pintype "passive"))
      (node (ref "SCL17") (pin "1") (pinfunction "P_1") (pintype "passive"))
      (node (ref "SCL18") (pin "1") (pinfunction "P_1") (pintype "passive"))
      (node (ref "SCL19") (pin "1") (pinfunction "P_1") (pintype "passive"))
      (node (ref "SCL2") (pin "1") (pinfunction "P_1") (pintype "passive"))
      (node (ref "SCL20") (pin "1") (pinfunction "P_1") (pintype "passive"))
      (node (ref "SCL21") (pin "1") (pinfunction "P_1") (pintype "passive"))
      (node (ref "SCL22") (pin "1") (pinfunction "P_1") (pintype "passive"))
      (node (ref "SCL23") (pin "1") (pinfunction "P_1") (pintype "passive"))
      (node (ref "SCL24") (pin "1") (pinfunction "P_1") (pintype "passive"))
      (node (ref "SCL3") (pin "1") (pinfunction "P_1") (pintype "passive"))
      (node (ref "SCL4") (pin "1") (pinfunction "P_1") (pintype "passive"))
      (node (ref "SCL5") (pin "1") (pinfunction "P_1") (pintype "passive"))
      (node (ref "SCL6") (pin "1") (pinfunction "P_1") (pintype "passive"))
      (node (ref "SCL7") (pin "1") (pinfunction "P_1") (pintype "passive"))
      (node (ref "SCL8") (pin "1") (pinfunction "P_1") (pintype "passive"))
      (node (ref "SCL9") (pin "1") (pinfunction "P_1") (pintype "passive"))
    )
    (net (code "56") (name "SDA") (class "Default")
      (node (ref "ARD-SDA") (pin "1") (pinfunction "P_1") (pintype "passive"))
      (node (ref "IC1") (pin "2") (pinfunction "SDA_2") (pintype "bidirectional"))
      (node (ref "IC2") (pin "2") (pinfunction "SDA_2") (pintype "bidirectional"))
      (node (ref "IC3") (pin "2") (pinfunction "SDA_2") (pintype "bidirectional"))
      (node (ref "PAD100") (pin "1") (pinfunction "P_1") (pintype "passive"))
      (node (ref "PAD12") (pin "1") (pinfunction "P_1") (pintype "passive"))
      (node (ref "PAD16") (pin "1") (pinfunction "P_1") (pintype "passive"))
      (node (ref "PAD20") (pin "1") (pinfunction "P_1") (pintype "passive"))
      (node (ref "PAD24") (pin "1") (pinfunction "P_1") (pintype "passive"))
      (node (ref "PAD28") (pin "1") (pinfunction "P_1") (pintype "passive"))
      (node (ref "PAD32") (pin "1") (pinfunction "P_1") (pintype "passive"))
      (node (ref "PAD36") (pin "1") (pinfunction "P_1") (pintype "passive"))
      (node (ref "PAD4") (pin "1") (pinfunction "P_1") (pintype "passive"))
      (node (ref "PAD40") (pin "1") (pinfunction "P_1") (pintype "passive"))
      (node (ref "PAD44") (pin "1") (pinfunction "P_1") (pintype "passive"))
      (node (ref "PAD48") (pin "1") (pinfunction "P_1") (pintype "passive"))
      (node (ref "PAD52") (pin "1") (pinfunction "P_1") (pintype "passive"))
      (node (ref "PAD56") (pin "1") (pinfunction "P_1") (pintype "passive"))
      (node (ref "PAD60") (pin "1") (pinfunction "P_1") (pintype "passive"))
      (node (ref "PAD64") (pin "1") (pinfunction "P_1") (pintype "passive"))
      (node (ref "PAD68") (pin "1") (pinfunction "P_1") (pintype "passive"))
      (node (ref "PAD72") (pin "1") (pinfunction "P_1") (pintype "passive"))
      (node (ref "PAD76") (pin "1") (pinfunction "P_1") (pintype "passive"))
      (node (ref "PAD8") (pin "1") (pinfunction "P_1") (pintype "passive"))
      (node (ref "PAD80") (pin "1") (pinfunction "P_1") (pintype "passive"))
      (node (ref "PAD84") (pin "1") (pinfunction "P_1") (pintype "passive"))
      (node (ref "PAD88") (pin "1") (pinfunction "P_1") (pintype "passive"))
      (node (ref "PAD92") (pin "1") (pinfunction "P_1") (pintype "passive"))
      (node (ref "PAD96") (pin "1") (pinfunction "P_1") (pintype "passive"))
      (node (ref "R10") (pin "P$1") (pinfunction "1_P$1") (pintype "passive"))
      (node (ref "R35") (pin "P$1") (pinfunction "1_P$1") (pintype "passive"))
      (node (ref "R6") (pin "P$1") (pinfunction "1_P$1") (pintype "passive"))
      (node (ref "R7") (pin "P$1") (pinfunction "1_P$1") (pintype "passive"))
      (node (ref "R8") (pin "P$1") (pinfunction "1_P$1") (pintype "passive"))
      (node (ref "R9") (pin "P$1") (pinfunction "1_P$1") (pintype "passive"))
      (node (ref "SDA") (pin "1") (pinfunction "P_1") (pintype "passive"))
      (node (ref "SDA1") (pin "1") (pinfunction "P_1") (pintype "passive"))
      (node (ref "SDA10") (pin "1") (pinfunction "P_1") (pintype "passive"))
      (node (ref "SDA11") (pin "1") (pinfunction "P_1") (pintype "passive"))
      (node (ref "SDA12") (pin "1") (pinfunction "P_1") (pintype "passive"))
      (node (ref "SDA13") (pin "1") (pinfunction "P_1") (pintype "passive"))
      (node (ref "SDA14") (pin "1") (pinfunction "P_1") (pintype "passive"))
      (node (ref "SDA15") (pin "1") (pinfunction "P_1") (pintype "passive"))
      (node (ref "SDA16") (pin "1") (pinfunction "P_1") (pintype "passive"))
      (node (ref "SDA17") (pin "1") (pinfunction "P_1") (pintype "passive"))
      (node (ref "SDA18") (pin "1") (pinfunction "P_1") (pintype "passive"))
      (node (ref "SDA19") (pin "1") (pinfunction "P_1") (pintype "passive"))
      (node (ref "SDA2") (pin "1") (pinfunction "P_1") (pintype "passive"))
      (node (ref "SDA20") (pin "1") (pinfunction "P_1") (pintype "passive"))
      (node (ref "SDA21") (pin "1") (pinfunction "P_1") (pintype "passive"))
      (node (ref "SDA22") (pin "1") (pinfunction "P_1") (pintype "passive"))
      (node (ref "SDA23") (pin "1") (pinfunction "P_1") (pintype "passive"))
      (node (ref "SDA24") (pin "1") (pinfunction "P_1") (pintype "passive"))
      (node (ref "SDA3") (pin "1") (pinfunction "P_1") (pintype "passive"))
      (node (ref "SDA4") (pin "1") (pinfunction "P_1") (pintype "passive"))
      (node (ref "SDA5") (pin "1") (pinfunction "P_1") (pintype "passive"))
      (node (ref "SDA6") (pin "1") (pinfunction "P_1") (pintype "passive"))
      (node (ref "SDA7") (pin "1") (pinfunction "P_1") (pintype "passive"))
      (node (ref "SDA8") (pin "1") (pinfunction "P_1") (pintype "passive"))
      (node (ref "SDA9") (pin "1") (pinfunction "P_1") (pintype "passive"))
    )
    (net (code "57") (name "VCC") (class "Default")
      (node (ref "ARD-VCC") (pin "1") (pinfunction "P_1") (pintype "passive"))
      (node (ref "DECOUP-CAP") (pin "P$1") (pinfunction "1_P$1") (pintype "passive"))
      (node (ref "PAD1") (pin "1") (pinfunction "P_1") (pintype "passive"))
      (node (ref "PAD13") (pin "1") (pinfunction "P_1") (pintype "passive"))
      (node (ref "PAD17") (pin "1") (pinfunction "P_1") (pintype "passive"))
      (node (ref "PAD21") (pin "1") (pinfunction "P_1") (pintype "passive"))
      (node (ref "PAD25") (pin "1") (pinfunction "P_1") (pintype "passive"))
      (node (ref "PAD29") (pin "1") (pinfunction "P_1") (pintype "passive"))
      (node (ref "PAD33") (pin "1") (pinfunction "P_1") (pintype "passive"))
      (node (ref "PAD37") (pin "1") (pinfunction "P_1") (pintype "passive"))
      (node (ref "PAD41") (pin "1") (pinfunction "P_1") (pintype "passive"))
      (node (ref "PAD45") (pin "1") (pinfunction "P_1") (pintype "passive"))
      (node (ref "PAD49") (pin "1") (pinfunction "P_1") (pintype "passive"))
      (node (ref "PAD5") (pin "1") (pinfunction "P_1") (pintype "passive"))
      (node (ref "PAD53") (pin "1") (pinfunction "P_1") (pintype "passive"))
      (node (ref "PAD57") (pin "1") (pinfunction "P_1") (pintype "passive"))
      (node (ref "PAD61") (pin "1") (pinfunction "P_1") (pintype "passive"))
      (node (ref "PAD65") (pin "1") (pinfunction "P_1") (pintype "passive"))
      (node (ref "PAD69") (pin "1") (pinfunction "P_1") (pintype "passive"))
      (node (ref "PAD73") (pin "1") (pinfunction "P_1") (pintype "passive"))
      (node (ref "PAD77") (pin "1") (pinfunction "P_1") (pintype "passive"))
      (node (ref "PAD81") (pin "1") (pinfunction "P_1") (pintype "passive"))
      (node (ref "PAD85") (pin "1") (pinfunction "P_1") (pintype "passive"))
      (node (ref "PAD89") (pin "1") (pinfunction "P_1") (pintype "passive"))
      (node (ref "PAD9") (pin "1") (pinfunction "P_1") (pintype "passive"))
      (node (ref "PAD93") (pin "1") (pinfunction "P_1") (pintype "passive"))
      (node (ref "PAD97") (pin "1") (pinfunction "P_1") (pintype "passive"))
      (node (ref "VCC") (pin "1") (pinfunction "P_1") (pintype "passive"))
      (node (ref "VCC1") (pin "1") (pinfunction "P_1") (pintype "passive"))
      (node (ref "VCC10") (pin "1") (pinfunction "P_1") (pintype "passive"))
      (node (ref "VCC11") (pin "1") (pinfunction "P_1") (pintype "passive"))
      (node (ref "VCC12") (pin "1") (pinfunction "P_1") (pintype "passive"))
      (node (ref "VCC13") (pin "1") (pinfunction "P_1") (pintype "passive"))
      (node (ref "VCC14") (pin "1") (pinfunction "P_1") (pintype "passive"))
      (node (ref "VCC15") (pin "1") (pinfunction "P_1") (pintype "passive"))
      (node (ref "VCC16") (pin "1") (pinfunction "P_1") (pintype "passive"))
      (node (ref "VCC17") (pin "1") (pinfunction "P_1") (pintype "passive"))
      (node (ref "VCC18") (pin "1") (pinfunction "P_1") (pintype "passive"))
      (node (ref "VCC19") (pin "1") (pinfunction "P_1") (pintype "passive"))
      (node (ref "VCC2") (pin "1") (pinfunction "P_1") (pintype "passive"))
      (node (ref "VCC20") (pin "1") (pinfunction "P_1") (pintype "passive"))
      (node (ref "VCC21") (pin "1") (pinfunction "P_1") (pintype "passive"))
      (node (ref "VCC22") (pin "1") (pinfunction "P_1") (pintype "passive"))
      (node (ref "VCC23") (pin "1") (pinfunction "P_1") (pintype "passive"))
      (node (ref "VCC24") (pin "1") (pinfunction "P_1") (pintype "passive"))
      (node (ref "VCC3") (pin "1") (pinfunction "P_1") (pintype "passive"))
      (node (ref "VCC4") (pin "1") (pinfunction "P_1") (pintype "passive"))
      (node (ref "VCC5") (pin "1") (pinfunction "P_1") (pintype "passive"))
      (node (ref "VCC6") (pin "1") (pinfunction "P_1") (pintype "passive"))
      (node (ref "VCC7") (pin "1") (pinfunction "P_1") (pintype "passive"))
      (node (ref "VCC8") (pin "1") (pinfunction "P_1") (pintype "passive"))
      (node (ref "VCC9") (pin "1") (pinfunction "P_1") (pintype "passive"))
    )
  )
)
